# 28pins_Antariksh_unoR3_V1I1_Schematic.net
KiCad netlist of a schematic drawn in Altium Designer
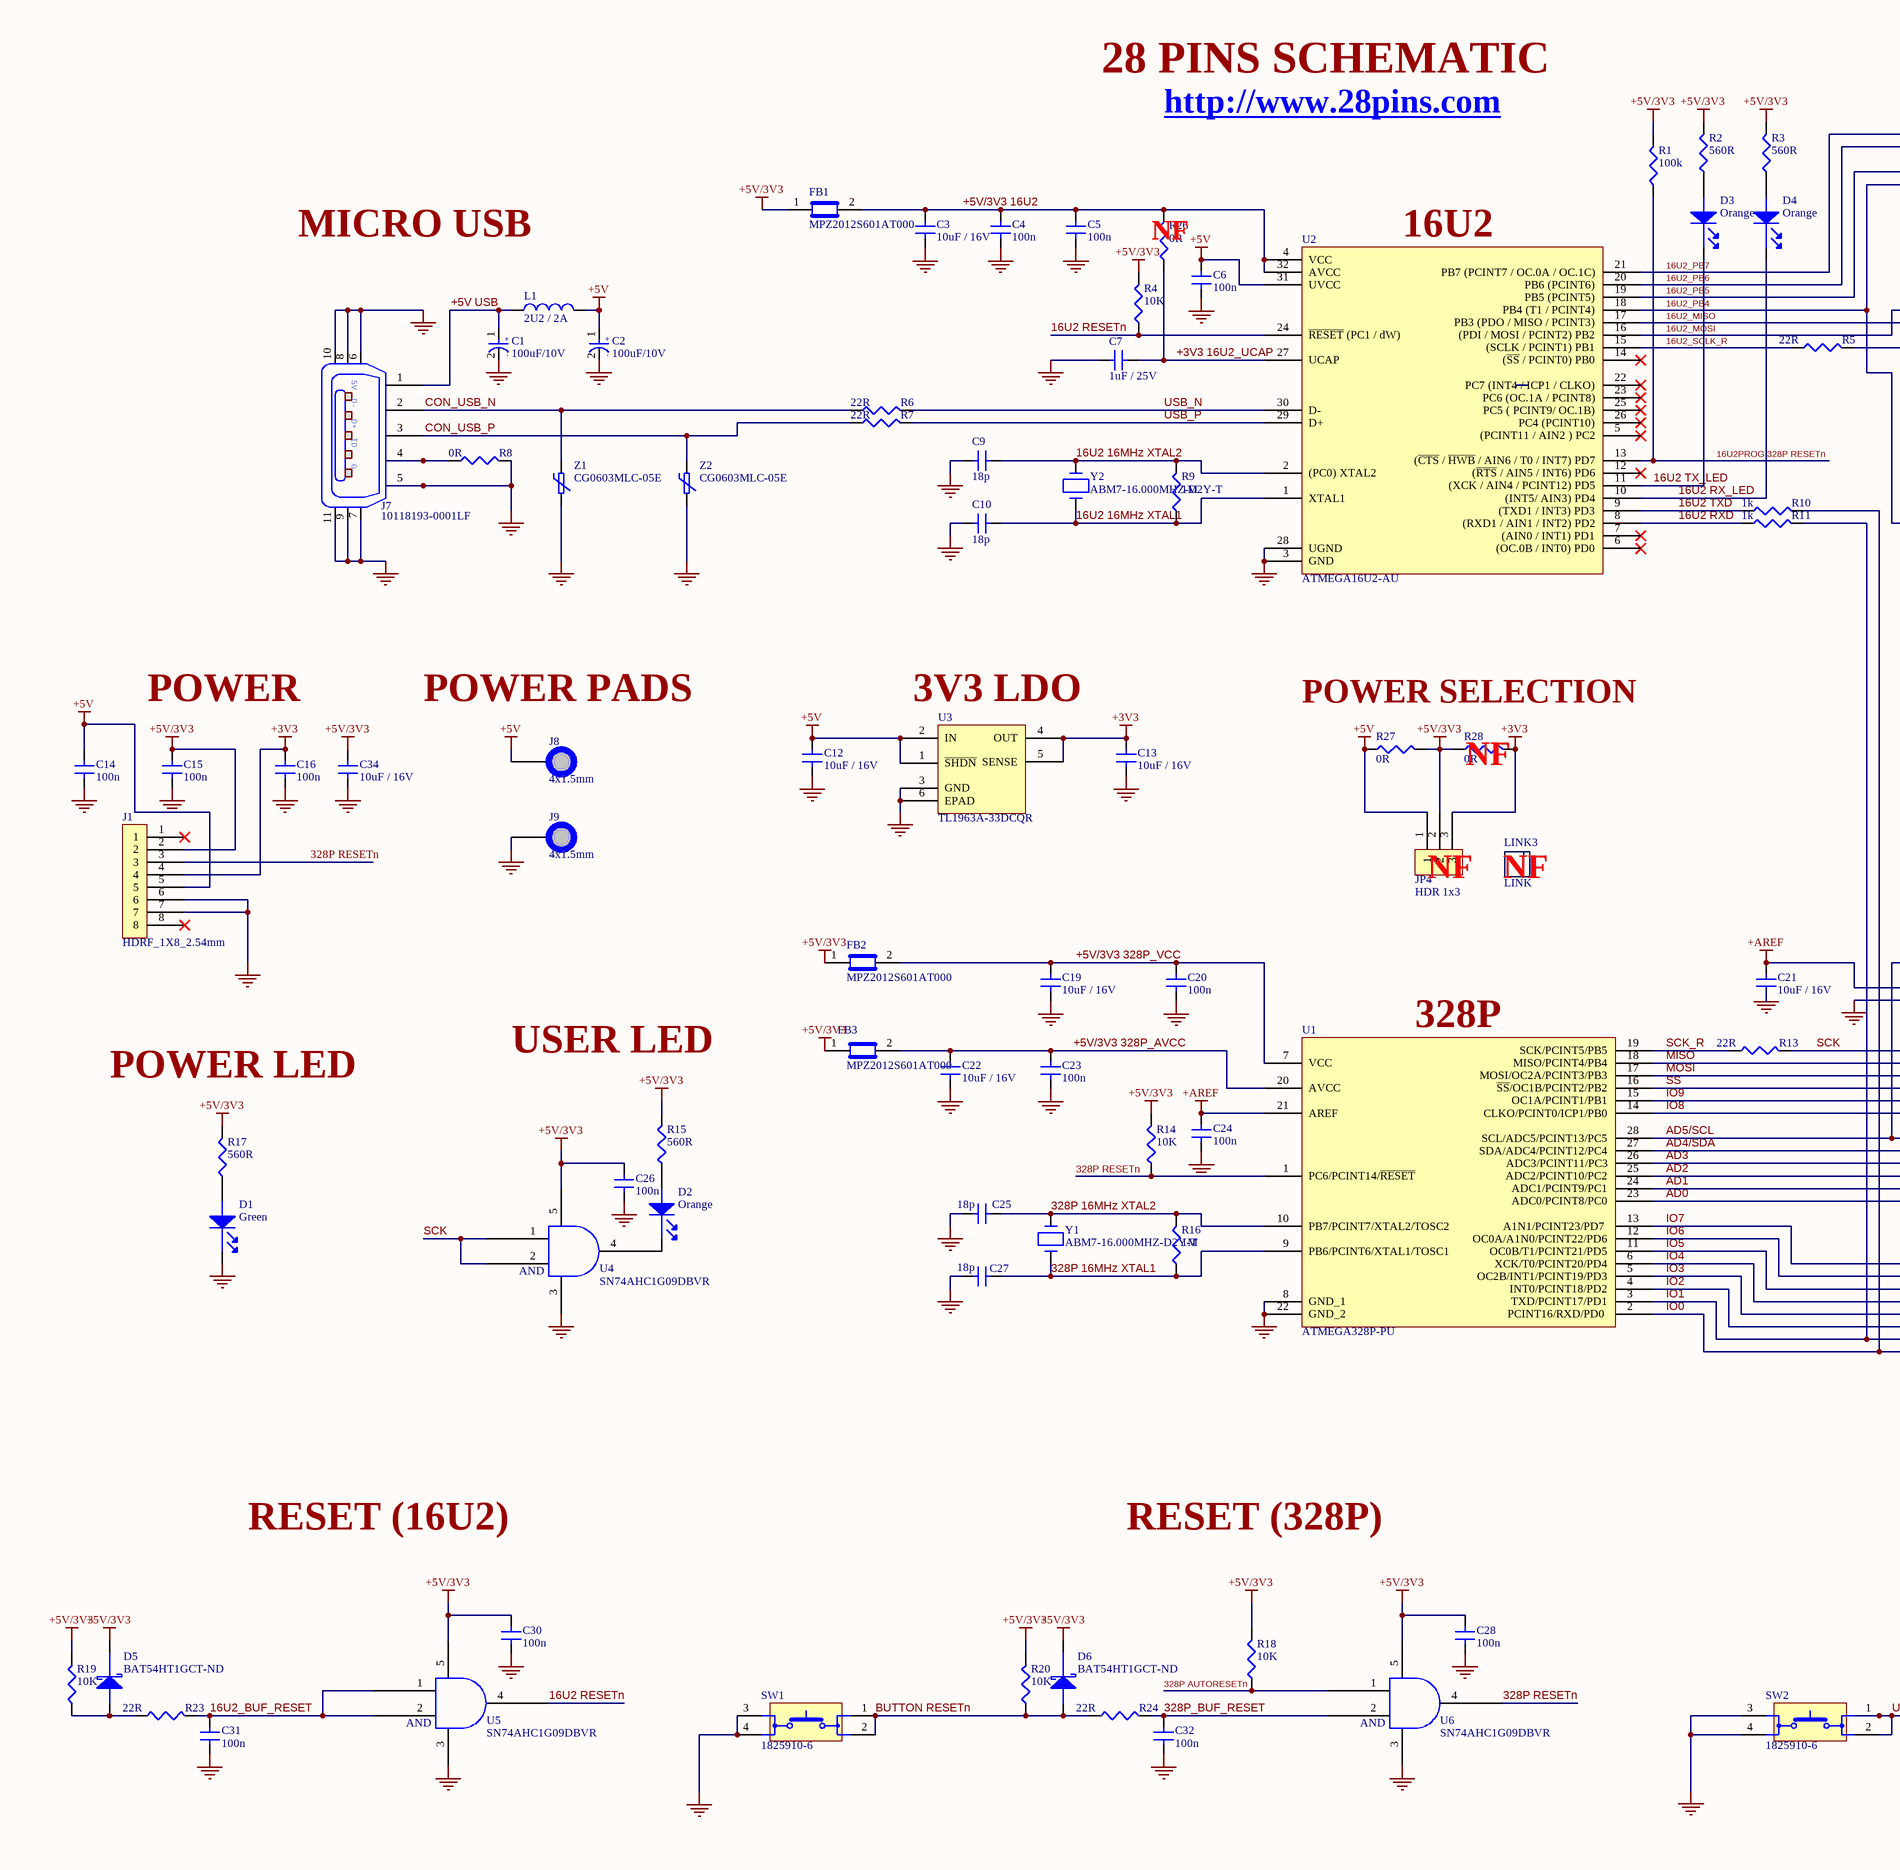
[diagram p0: 28pins_Antariksh_unoR3_V1I1_Schematic.SchDoc, left]
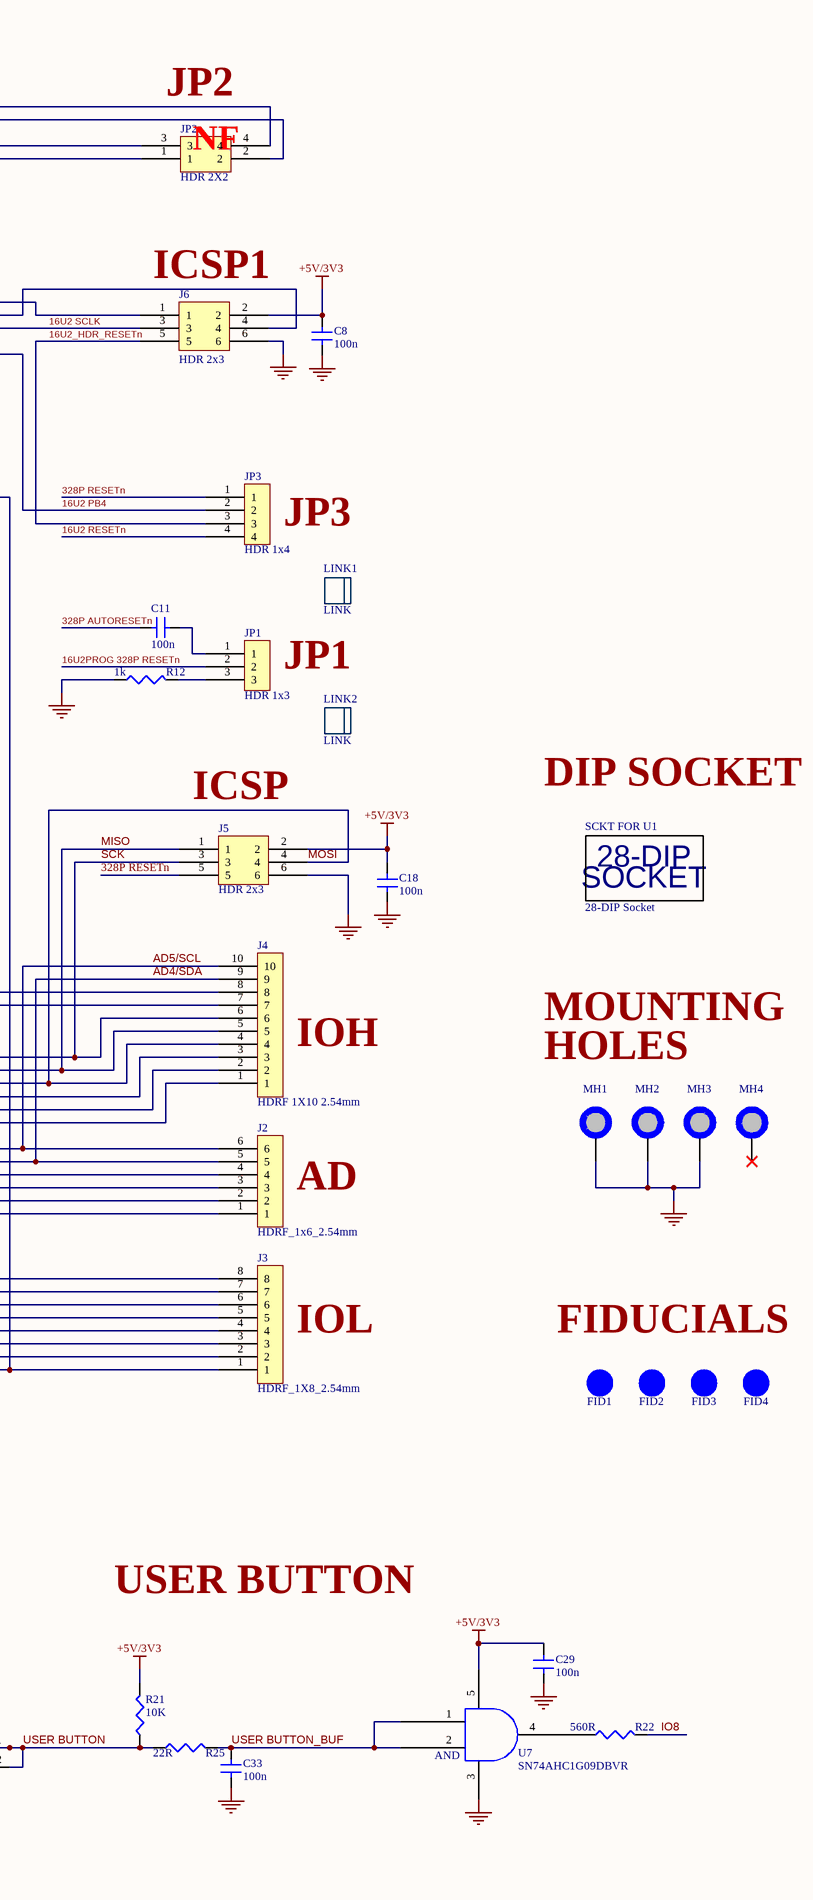
[diagram p1: 28pins_Antariksh_unoR3_V1I1_Schematic.SchDoc, right]

(export (version "E")
  (design (tool "Eeschema 10.0.6"))
  (components
    (comp (ref "C1")
      (value "100uF/10V")
      (footprint "C_ALU_C_SIZE")
      (description "Radial Can - SMD ALUMINUM ELECTROLYTIC CAPACITOR S 10V 100muF ±20% 0.197Dia 5.00mm")
      (fields
        (field (name "MANUFACTURER") "Panasonic")
        (field (name "MANUFACTURER PART NUMBER") "EEE-1AA101WR")
      )
      (libsource (lib "28pins_Antariksh_unoR3_V1I1_PCB") (part "EEE-1AA101WR"))
    )
    (comp (ref "C2")
      (value "100uF/10V")
      (footprint "C_ALU_C_SIZE")
      (description "Radial Can - SMD ALUMINUM ELECTROLYTIC CAPACITOR S 10V 100muF ±20% 0.197Dia 5.00mm")
      (fields
        (field (name "MANUFACTURER") "Panasonic")
        (field (name "MANUFACTURER PART NUMBER") "EEE-1AA101WR")
      )
      (libsource (lib "28pins_Antariksh_unoR3_V1I1_PCB") (part "EEE-1AA101WR"))
    )
    (comp (ref "C3")
      (value "10uF / 16V")
      (footprint "C0805")
      (fields
        (field (name "MANUFACTURER") "TDK")
        (field (name "MANUFACTURER PART NUMBER") "C2012X5R1C106M125AC")
        (field (name "TOLERANCE") "20%")
      )
      (libsource (lib "28pins_Antariksh_unoR3_V1I1_PCB") (part "C2012X5R1C106M125AC"))
    )
    (comp (ref "C4")
      (value "100n")
      (footprint "C0805")
      (description "C Series 0805 0.1 uF 50 V ±10 % Tolerance X7R SMT Multilayer Ceramic Capacitor")
      (fields
        (field (name "MANUFACTURER") "TDK")
        (field (name "MANUFACTURER PART NUMBER") "C2012X7R1H104K085AA")
      )
      (libsource (lib "28pins_Antariksh_unoR3_V1I1_PCB") (part "C2012X7R1H104K085AA"))
    )
    (comp (ref "C5")
      (value "100n")
      (footprint "C0805")
      (description "C Series 0805 0.1 uF 50 V ±10 % Tolerance X7R SMT Multilayer Ceramic Capacitor")
      (fields
        (field (name "MANUFACTURER") "TDK")
        (field (name "MANUFACTURER PART NUMBER") "C2012X7R1H104K085AA")
      )
      (libsource (lib "28pins_Antariksh_unoR3_V1I1_PCB") (part "C2012X7R1H104K085AA"))
    )
    (comp (ref "C6")
      (value "100n")
      (footprint "C0805")
      (description "C Series 0805 0.1 uF 50 V ±10 % Tolerance X7R SMT Multilayer Ceramic Capacitor")
      (fields
        (field (name "MANUFACTURER") "TDK")
        (field (name "MANUFACTURER PART NUMBER") "C2012X7R1H104K085AA")
      )
      (libsource (lib "28pins_Antariksh_unoR3_V1I1_PCB") (part "C2012X7R1H104K085AA"))
    )
    (comp (ref "C7")
      (value "1uF / 25V")
      (footprint "C0805")
      (description "C Series 0805 1 uF 25 V ±10% Tolerance X5R SMT Multilayer Ceramic Capacitor")
      (fields
        (field (name "MANUFACTURER") "TDK")
        (field (name "MANUFACTURER PART NUMBER") "C2012X5R1E105K125AA")
      )
      (libsource (lib "28pins_Antariksh_unoR3_V1I1_PCB") (part "C2012X5R1E105K125AA"))
    )
    (comp (ref "C8")
      (value "100n")
      (footprint "C0805")
      (description "C Series 0805 0.1 uF 50 V ±10 % Tolerance X7R SMT Multilayer Ceramic Capacitor")
      (fields
        (field (name "MANUFACTURER") "TDK")
        (field (name "MANUFACTURER PART NUMBER") "C2012X7R1H104K085AA")
      )
      (libsource (lib "28pins_Antariksh_unoR3_V1I1_PCB") (part "C2012X7R1H104K085AA"))
    )
    (comp (ref "C9")
      (value "18p")
      (footprint "C0805")
      (description "50V 120pF NP0 ±5% 0805 Multilayer Ceramic Capacitors MLCC - SMD/SMT ROHS")
      (fields
        (field (name "MANUFACTURER") "Yageo Group")
        (field (name "MANUFACTURER PART NUMBER") "CC0805JRNPO9BN121")
      )
      (libsource (lib "28pins_Antariksh_unoR3_V1I1_PCB") (part "CC0805JRNPO9BN121"))
    )
    (comp (ref "C10")
      (value "18p")
      (footprint "C0805")
      (description "50V 120pF NP0 ±5% 0805 Multilayer Ceramic Capacitors MLCC - SMD/SMT ROHS")
      (fields
        (field (name "MANUFACTURER") "Yageo Group")
        (field (name "MANUFACTURER PART NUMBER") "CC0805JRNPO9BN121")
      )
      (libsource (lib "28pins_Antariksh_unoR3_V1I1_PCB") (part "CC0805JRNPO9BN121"))
    )
    (comp (ref "C11")
      (value "100n")
      (footprint "C0805")
      (description "C Series 0805 0.1 uF 50 V ±10 % Tolerance X7R SMT Multilayer Ceramic Capacitor")
      (fields
        (field (name "MANUFACTURER") "TDK")
        (field (name "MANUFACTURER PART NUMBER") "C2012X7R1H104K085AA")
      )
      (libsource (lib "28pins_Antariksh_unoR3_V1I1_PCB") (part "C2012X7R1H104K085AA"))
    )
    (comp (ref "C12")
      (value "10uF / 16V")
      (footprint "C0805")
      (fields
        (field (name "MANUFACTURER") "TDK")
        (field (name "MANUFACTURER PART NUMBER") "C2012X5R1C106M125AC")
        (field (name "TOLERANCE") "20%")
      )
      (libsource (lib "28pins_Antariksh_unoR3_V1I1_PCB") (part "C2012X5R1C106M125AC"))
    )
    (comp (ref "C13")
      (value "10uF / 16V")
      (footprint "C0805")
      (fields
        (field (name "MANUFACTURER") "TDK")
        (field (name "MANUFACTURER PART NUMBER") "C2012X5R1C106M125AC")
        (field (name "TOLERANCE") "20%")
      )
      (libsource (lib "28pins_Antariksh_unoR3_V1I1_PCB") (part "C2012X5R1C106M125AC"))
    )
    (comp (ref "C14")
      (value "100n")
      (footprint "C0805")
      (description "C Series 0805 0.1 uF 50 V ±10 % Tolerance X7R SMT Multilayer Ceramic Capacitor")
      (fields
        (field (name "MANUFACTURER") "TDK")
        (field (name "MANUFACTURER PART NUMBER") "C2012X7R1H104K085AA")
      )
      (libsource (lib "28pins_Antariksh_unoR3_V1I1_PCB") (part "C2012X7R1H104K085AA"))
    )
    (comp (ref "C15")
      (value "100n")
      (footprint "C0805")
      (description "C Series 0805 0.1 uF 50 V ±10 % Tolerance X7R SMT Multilayer Ceramic Capacitor")
      (fields
        (field (name "MANUFACTURER") "TDK")
        (field (name "MANUFACTURER PART NUMBER") "C2012X7R1H104K085AA")
      )
      (libsource (lib "28pins_Antariksh_unoR3_V1I1_PCB") (part "C2012X7R1H104K085AA"))
    )
    (comp (ref "C16")
      (value "100n")
      (footprint "C0805")
      (description "C Series 0805 0.1 uF 50 V ±10 % Tolerance X7R SMT Multilayer Ceramic Capacitor")
      (fields
        (field (name "MANUFACTURER") "TDK")
        (field (name "MANUFACTURER PART NUMBER") "C2012X7R1H104K085AA")
      )
      (libsource (lib "28pins_Antariksh_unoR3_V1I1_PCB") (part "C2012X7R1H104K085AA"))
    )
    (comp (ref "C18")
      (value "100n")
      (footprint "C0805")
      (description "C Series 0805 0.1 uF 50 V ±10 % Tolerance X7R SMT Multilayer Ceramic Capacitor")
      (fields
        (field (name "MANUFACTURER") "TDK")
        (field (name "MANUFACTURER PART NUMBER") "C2012X7R1H104K085AA")
      )
      (libsource (lib "28pins_Antariksh_unoR3_V1I1_PCB") (part "C2012X7R1H104K085AA"))
    )
    (comp (ref "C19")
      (value "10uF / 16V")
      (footprint "C0805")
      (fields
        (field (name "MANUFACTURER") "TDK")
        (field (name "MANUFACTURER PART NUMBER") "C2012X5R1C106M125AC")
        (field (name "TOLERANCE") "20%")
      )
      (libsource (lib "28pins_Antariksh_unoR3_V1I1_PCB") (part "C2012X5R1C106M125AC"))
    )
    (comp (ref "C20")
      (value "100n")
      (footprint "C0805")
      (description "C Series 0805 0.1 uF 50 V ±10 % Tolerance X7R SMT Multilayer Ceramic Capacitor")
      (fields
        (field (name "MANUFACTURER") "TDK")
        (field (name "MANUFACTURER PART NUMBER") "C2012X7R1H104K085AA")
      )
      (libsource (lib "28pins_Antariksh_unoR3_V1I1_PCB") (part "C2012X7R1H104K085AA"))
    )
    (comp (ref "C21")
      (value "10uF / 16V")
      (footprint "C0805")
      (fields
        (field (name "MANUFACTURER") "TDK")
        (field (name "MANUFACTURER PART NUMBER") "C2012X5R1C106M125AC")
        (field (name "TOLERANCE") "20%")
      )
      (libsource (lib "28pins_Antariksh_unoR3_V1I1_PCB") (part "C2012X5R1C106M125AC"))
    )
    (comp (ref "C22")
      (value "10uF / 16V")
      (footprint "C0805")
      (fields
        (field (name "MANUFACTURER") "TDK")
        (field (name "MANUFACTURER PART NUMBER") "C2012X5R1C106M125AC")
        (field (name "TOLERANCE") "20%")
      )
      (libsource (lib "28pins_Antariksh_unoR3_V1I1_PCB") (part "C2012X5R1C106M125AC"))
    )
    (comp (ref "C23")
      (value "100n")
      (footprint "C0805")
      (description "C Series 0805 0.1 uF 50 V ±10 % Tolerance X7R SMT Multilayer Ceramic Capacitor")
      (fields
        (field (name "MANUFACTURER") "TDK")
        (field (name "MANUFACTURER PART NUMBER") "C2012X7R1H104K085AA")
      )
      (libsource (lib "28pins_Antariksh_unoR3_V1I1_PCB") (part "C2012X7R1H104K085AA"))
    )
    (comp (ref "C24")
      (value "100n")
      (footprint "C0805")
      (description "C Series 0805 0.1 uF 50 V ±10 % Tolerance X7R SMT Multilayer Ceramic Capacitor")
      (fields
        (field (name "MANUFACTURER") "TDK")
        (field (name "MANUFACTURER PART NUMBER") "C2012X7R1H104K085AA")
      )
      (libsource (lib "28pins_Antariksh_unoR3_V1I1_PCB") (part "C2012X7R1H104K085AA"))
    )
    (comp (ref "C25")
      (value "18p")
      (footprint "C0805")
      (description "50V 120pF NP0 ±5% 0805 Multilayer Ceramic Capacitors MLCC - SMD/SMT ROHS")
      (fields
        (field (name "MANUFACTURER") "Yageo Group")
        (field (name "MANUFACTURER PART NUMBER") "CC0805JRNPO9BN121")
      )
      (libsource (lib "28pins_Antariksh_unoR3_V1I1_PCB") (part "CC0805JRNPO9BN121"))
    )
    (comp (ref "C26")
      (value "100n")
      (footprint "C0805")
      (description "C Series 0805 0.1 uF 50 V ±10 % Tolerance X7R SMT Multilayer Ceramic Capacitor")
      (fields
        (field (name "MANUFACTURER") "TDK")
        (field (name "MANUFACTURER PART NUMBER") "C2012X7R1H104K085AA")
      )
      (libsource (lib "28pins_Antariksh_unoR3_V1I1_PCB") (part "C2012X7R1H104K085AA"))
    )
    (comp (ref "C27")
      (value "18p")
      (footprint "C0805")
      (description "50V 120pF NP0 ±5% 0805 Multilayer Ceramic Capacitors MLCC - SMD/SMT ROHS")
      (fields
        (field (name "MANUFACTURER") "Yageo Group")
        (field (name "MANUFACTURER PART NUMBER") "CC0805JRNPO9BN121")
      )
      (libsource (lib "28pins_Antariksh_unoR3_V1I1_PCB") (part "CC0805JRNPO9BN121"))
    )
    (comp (ref "C28")
      (value "100n")
      (footprint "C0805")
      (description "C Series 0805 0.1 uF 50 V ±10 % Tolerance X7R SMT Multilayer Ceramic Capacitor")
      (fields
        (field (name "MANUFACTURER") "TDK")
        (field (name "MANUFACTURER PART NUMBER") "C2012X7R1H104K085AA")
      )
      (libsource (lib "28pins_Antariksh_unoR3_V1I1_PCB") (part "C2012X7R1H104K085AA"))
    )
    (comp (ref "C29")
      (value "100n")
      (footprint "C0805")
      (description "C Series 0805 0.1 uF 50 V ±10 % Tolerance X7R SMT Multilayer Ceramic Capacitor")
      (fields
        (field (name "MANUFACTURER") "TDK")
        (field (name "MANUFACTURER PART NUMBER") "C2012X7R1H104K085AA")
      )
      (libsource (lib "28pins_Antariksh_unoR3_V1I1_PCB") (part "C2012X7R1H104K085AA"))
    )
    (comp (ref "C30")
      (value "100n")
      (footprint "C0805")
      (description "C Series 0805 0.1 uF 50 V ±10 % Tolerance X7R SMT Multilayer Ceramic Capacitor")
      (fields
        (field (name "MANUFACTURER") "TDK")
        (field (name "MANUFACTURER PART NUMBER") "C2012X7R1H104K085AA")
      )
      (libsource (lib "28pins_Antariksh_unoR3_V1I1_PCB") (part "C2012X7R1H104K085AA"))
    )
    (comp (ref "C31")
      (value "100n")
      (footprint "C0805")
      (description "C Series 0805 0.1 uF 50 V ±10 % Tolerance X7R SMT Multilayer Ceramic Capacitor")
      (fields
        (field (name "MANUFACTURER") "TDK")
        (field (name "MANUFACTURER PART NUMBER") "C2012X7R1H104K085AA")
      )
      (libsource (lib "28pins_Antariksh_unoR3_V1I1_PCB") (part "C2012X7R1H104K085AA"))
    )
    (comp (ref "C32")
      (value "100n")
      (footprint "C0805")
      (description "C Series 0805 0.1 uF 50 V ±10 % Tolerance X7R SMT Multilayer Ceramic Capacitor")
      (fields
        (field (name "MANUFACTURER") "TDK")
        (field (name "MANUFACTURER PART NUMBER") "C2012X7R1H104K085AA")
      )
      (libsource (lib "28pins_Antariksh_unoR3_V1I1_PCB") (part "C2012X7R1H104K085AA"))
    )
    (comp (ref "C33")
      (value "100n")
      (footprint "C0805")
      (description "C Series 0805 0.1 uF 50 V ±10 % Tolerance X7R SMT Multilayer Ceramic Capacitor")
      (fields
        (field (name "MANUFACTURER") "TDK")
        (field (name "MANUFACTURER PART NUMBER") "C2012X7R1H104K085AA")
      )
      (libsource (lib "28pins_Antariksh_unoR3_V1I1_PCB") (part "C2012X7R1H104K085AA"))
    )
    (comp (ref "C34")
      (value "10uF / 16V")
      (footprint "C0805")
      (fields
        (field (name "MANUFACTURER") "TDK")
        (field (name "MANUFACTURER PART NUMBER") "C2012X5R1C106M125AC")
        (field (name "TOLERANCE") "20%")
      )
      (libsource (lib "28pins_Antariksh_unoR3_V1I1_PCB") (part "C2012X5R1C106M125AC"))
    )
    (comp (ref "D1")
      (value "Green")
      (footprint "LED_0603")
      (description "LED Uni-Color Green 572nm 2-Pin Chip 0603(1608Metric) T/R")
      (fields
        (field (name "MANUFACTURER") "Osram")
        (field (name "MANUFACTURER PART NUMBER") "LG L29K-G2J1-24-0-2-R18-Z")
      )
      (libsource (lib "28pins_Antariksh_unoR3_V1I1_PCB") (part "LG L29K-G2J1-24-0-2-R18-Z"))
    )
    (comp (ref "D2")
      (value "Orange")
      (footprint "LED_0603")
      (description "LED Uni-Color Orange 610nm Automotive 2-Pin Chip 0603(1608Metric) T/R")
      (fields
        (field (name "MANUFACTURER") "Osram")
        (field (name "MANUFACTURER PART NUMBER") "LO L29K-H2K1-24-0-2-R18-Z")
      )
      (libsource (lib "28pins_Antariksh_unoR3_V1I1_PCB") (part "LO L29K-H2K1-24-0-2-R18-Z"))
    )
    (comp (ref "D3")
      (value "Orange")
      (footprint "LED_0603")
      (description "LED Uni-Color Orange 610nm Automotive 2-Pin Chip 0603(1608Metric) T/R")
      (fields
        (field (name "MANUFACTURER") "Osram")
        (field (name "MANUFACTURER PART NUMBER") "LO L29K-H2K1-24-0-2-R18-Z")
      )
      (libsource (lib "28pins_Antariksh_unoR3_V1I1_PCB") (part "LO L29K-H2K1-24-0-2-R18-Z"))
    )
    (comp (ref "D4")
      (value "Orange")
      (footprint "LED_0603")
      (description "LED Uni-Color Orange 610nm Automotive 2-Pin Chip 0603(1608Metric) T/R")
      (fields
        (field (name "MANUFACTURER") "Osram")
        (field (name "MANUFACTURER PART NUMBER") "LO L29K-H2K1-24-0-2-R18-Z")
      )
      (libsource (lib "28pins_Antariksh_unoR3_V1I1_PCB") (part "LO L29K-H2K1-24-0-2-R18-Z"))
    )
    (comp (ref "D5")
      (value "BAT54HT1GCT-ND")
      (footprint "SOD323")
      (description "Small Signal Schottky Diode, Single, 30 V, 200 Ma, 800 Mv, 600 Ma, 150 C")
      (fields (field (name "MANUFACTURER") "onsemi") (field (name "MANUFACTURER PART NUMBER") "BAT54HT1G"))
      (libsource (lib "28pins_Antariksh_unoR3_V1I1_PCB") (part "BAT54HT1G"))
    )
    (comp (ref "D6")
      (value "BAT54HT1GCT-ND")
      (footprint "SOD323")
      (description "Small Signal Schottky Diode, Single, 30 V, 200 Ma, 800 Mv, 600 Ma, 150 C")
      (fields (field (name "MANUFACTURER") "onsemi") (field (name "MANUFACTURER PART NUMBER") "BAT54HT1G"))
      (libsource (lib "28pins_Antariksh_unoR3_V1I1_PCB") (part "BAT54HT1G"))
    )
    (comp (ref "FB1")
      (value "MPZ2012S601AT000")
      (footprint "C0805")
      (description "Ferrite Beads Multi-Layer Power 600Ohm 25% 100MHz 2A 100mOhm DCR 0805 T/R")
      (fields (field (name "MANUFACTURER") "TDK") (field (name "TOLERANCE") "25%"))
      (libsource (lib "28pins_Antariksh_unoR3_V1I1_PCB") (part "MPZ2012S601AT000"))
    )
    (comp (ref "FB2")
      (value "MPZ2012S601AT000")
      (footprint "C0805")
      (description "Ferrite Beads Multi-Layer Power 600Ohm 25% 100MHz 2A 100mOhm DCR 0805 T/R")
      (fields (field (name "MANUFACTURER") "TDK") (field (name "TOLERANCE") "25%"))
      (libsource (lib "28pins_Antariksh_unoR3_V1I1_PCB") (part "MPZ2012S601AT000"))
    )
    (comp (ref "FB3")
      (value "MPZ2012S601AT000")
      (footprint "C0805")
      (description "Ferrite Beads Multi-Layer Power 600Ohm 25% 100MHz 2A 100mOhm DCR 0805 T/R")
      (fields (field (name "MANUFACTURER") "TDK") (field (name "TOLERANCE") "25%"))
      (libsource (lib "28pins_Antariksh_unoR3_V1I1_PCB") (part "MPZ2012S601AT000"))
    )
    (comp (ref "FID1")
      (value "FID_1mm")
      (footprint "FID_40x120")
      (description "Fiducial 40mil Diameter, 120mil Mask")
      (libsource (lib "28pins_Antariksh_unoR3_V1I1_PCB") (part "FID_1mm"))
    )
    (comp (ref "FID2")
      (value "FID_1mm")
      (footprint "FID_40x120")
      (description "Fiducial 40mil Diameter, 120mil Mask")
      (libsource (lib "28pins_Antariksh_unoR3_V1I1_PCB") (part "FID_1mm"))
    )
    (comp (ref "FID3")
      (value "FID_1mm")
      (footprint "FID_40x120")
      (description "Fiducial 40mil Diameter, 120mil Mask")
      (libsource (lib "28pins_Antariksh_unoR3_V1I1_PCB") (part "FID_1mm"))
    )
    (comp (ref "FID4")
      (value "FID_1mm")
      (footprint "FID_40x120")
      (description "Fiducial 40mil Diameter, 120mil Mask")
      (libsource (lib "28pins_Antariksh_unoR3_V1I1_PCB") (part "FID_1mm"))
    )
    (comp (ref "J1")
      (value "HDRF_1X8_2.54mm")
      (footprint "HDR_F_1X8_2.54mm")
      (description "2.54mm (0.1) Pitch SIL Vertical PC Tail Socket Assembly, selective gold + tin, 8 contacts\"")
      (fields (field (name "MANUFACTURER") "Harwin") (field (name "MANUFACTURER PART NUMBER") "M20-7820842"))
      (libsource (lib "28pins_Antariksh_unoR3_V1I1_PCB") (part "M20-7820842"))
    )
    (comp (ref "J2")
      (value "HDRF_1x6_2.54mm")
      (footprint "HDR_F_1X6_2.54mm")
      (description "Conn Socket Strip Receptacle 6 Position 2.54mm Solder Straight Through Hole Tube")
      (fields (field (name "MANUFACTURER") "Harwin") (field (name "MANUFACTURER PART NUMBER") "M20-7820646"))
      (libsource (lib "28pins_Antariksh_unoR3_V1I1_PCB") (part "M20-7820646"))
    )
    (comp (ref "J3")
      (value "HDRF_1X8_2.54mm")
      (footprint "HDR_F_1X8_2.54mm")
      (description "2.54mm (0.1) Pitch SIL Vertical PC Tail Socket Assembly, selective gold + tin, 8 contacts\"")
      (fields (field (name "MANUFACTURER") "Harwin") (field (name "MANUFACTURER PART NUMBER") "M20-7820842"))
      (libsource (lib "") (part "M20-7820842_1"))
    )
    (comp (ref "J4")
      (value "HDRF 1X10 2.54mm")
      (footprint "HDR_F_1X10_2.54mm")
      (description "Conn Socket Strip Receptacle 10 Position 2.54mm Solder Straight Through Hole Tube")
      (fields (field (name "MANUFACTURER") "Harwin") (field (name "MANUFACTURER PART NUMBER") "M20-7821046"))
      (libsource (lib "28pins_Antariksh_unoR3_V1I1_PCB") (part "M20-7821046"))
    )
    (comp (ref "J5")
      (value "HDR 2x3")
      (footprint "HDR_2x3_2.54mm")
      (description "Conn; Rect; Header; Unshrouded; 6 Pos; 2.54mm Pitch; 2-Row; Thru-Hole; BergStik")
      (fields
        (field (name "MANUFACTURER") "Amphenol Communications Solutions")
        (field (name "MANUFACTURER PART NUMBER") "67997-106HLF")
      )
      (libsource (lib "28pins_Antariksh_unoR3_V1I1_PCB") (part "67997-106HLF"))
    )
    (comp (ref "J6")
      (value "HDR 2x3")
      (footprint "HDR_2x3_2.54mm")
      (description "Conn; Rect; Header; Unshrouded; 6 Pos; 2.54mm Pitch; 2-Row; Thru-Hole; BergStik")
      (fields
        (field (name "MANUFACTURER") "Amphenol Communications Solutions")
        (field (name "MANUFACTURER PART NUMBER") "67997-106HLF")
      )
      (libsource (lib "28pins_Antariksh_unoR3_V1I1_PCB") (part "67997-106HLF"))
    )
    (comp (ref "J7")
      (value "10118193-0001LF")
      (footprint "10118193")
      (description "USB - micro B USB 2.0 Receptacle Connector 5 Position Surface Mount, Right Angle, Horizontal")
      (fields (field (name "MANUFACTURER") "Amphenol Communications Solutions"))
      (libsource (lib "28pins_Antariksh_unoR3_V1I1_PCB") (part "10118193-0001LF"))
    )
    (comp (ref "J8")
      (value "4x1.5mm")
      (footprint "PAD_WITH_HOLE_4x1.5mm")
      (description "PAD WITH A HOLE 4x1.5mm")
      (libsource (lib "28pins_Antariksh_unoR3_V1I1_PCB") (part "PAD_WITH_HOLE_4x1.5mm"))
    )
    (comp (ref "J9")
      (value "4x1.5mm")
      (footprint "PAD_WITH_HOLE_4x1.5mm")
      (description "PAD WITH A HOLE 4x1.5mm")
      (libsource (lib "28pins_Antariksh_unoR3_V1I1_PCB") (part "PAD_WITH_HOLE_4x1.5mm"))
    )
    (comp (ref "JP1")
      (value "HDR 1x3")
      (footprint "HDR_1X3_2.54mm")
      (description "Conn Unshrouded Header HDR 3 POS 2.54mm Solder ST Top Entry Thru-Hole BergStik® Bulk")
      (fields
        (field (name "MANUFACTURER") "Amphenol Communications Solutions")
        (field (name "MANUFACTURER PART NUMBER") "68000-103HLF")
      )
      (libsource (lib "") (part "68000-103HLF_1"))
    )
    (comp (ref "JP2")
      (value "HDR 2X2")
      (footprint "HDR_2x2_2.54mm")
      (description "Conn Unshrouded Header HDR 4 POS 2.54mm Solder ST Top Entry Thru-Hole BergStik® Bulk")
      (fields
        (field (name "MANUFACTURER") "Amphenol Communications Solutions")
        (field (name "MANUFACTURER PART NUMBER") "67996-104HLF")
      )
      (libsource (lib "28pins_Antariksh_unoR3_V1I1_PCB") (part "67996-104HLF"))
    )
    (comp (ref "JP3")
      (value "HDR 1x4")
      (footprint "HDR_1X4_2.54mm")
      (description "Conn Unshrouded Header HDR 4 POS 2.54mm Solder ST Top Entry Thru-Hole BergStik® Bulk")
      (fields
        (field (name "MANUFACTURER") "Amphenol Communications Solutions")
        (field (name "MANUFACTURER PART NUMBER") "68001-204HLF")
      )
      (libsource (lib "28pins_Antariksh_unoR3_V1I1_PCB") (part "68001-204HLF"))
    )
    (comp (ref "JP4")
      (value "HDR 1x3")
      (footprint "HDR_1X3_2.54mm")
      (description "Conn Unshrouded Header HDR 3 POS 2.54mm Solder ST Top Entry Thru-Hole BergStik® Bulk")
      (fields
        (field (name "MANUFACTURER") "Amphenol Communications Solutions")
        (field (name "MANUFACTURER PART NUMBER") "68000-103HLF")
      )
      (libsource (lib "28pins_Antariksh_unoR3_V1I1_PCB") (part "68000-103HLF"))
    )
    (comp (ref "L1")
      (value "2U2 / 2A")
      (footprint "CL210_IND")
      (description "General Purpose Inductor, 2.2uH, 20%, 1 Element, Ferrite-Core, SMD, 1210")
      (fields
        (field (name "MANUFACTURER") "KEMET")
        (field (name "MANUFACTURER PART NUMBER") "L1210R2R2MDWIT")
      )
      (libsource (lib "28pins_Antariksh_unoR3_V1I1_PCB") (part "L1210R2R2MDWIT"))
    )
    (comp (ref "LINK1")
      (value "LINK")
      (description "2 Position 2.54 mm Centerline Single Circuit Open Top Jumper")
      (fields
        (field (name "MANUFACTURER") "Sullins")
        (field (name "MANUFACTURER PART NUMBER") "QPC02SXGN-RC")
      )
      (libsource (lib "28pins_Antariksh_unoR3_V1I1_PCB") (part "QPC02SXGN-RC"))
    )
    (comp (ref "LINK2")
      (value "LINK")
      (description "2 Position 2.54 mm Centerline Single Circuit Open Top Jumper")
      (fields
        (field (name "MANUFACTURER") "Sullins")
        (field (name "MANUFACTURER PART NUMBER") "QPC02SXGN-RC")
      )
      (libsource (lib "28pins_Antariksh_unoR3_V1I1_PCB") (part "QPC02SXGN-RC"))
    )
    (comp (ref "LINK3")
      (value "LINK")
      (description "2 Position 2.54 mm Centerline Single Circuit Open Top Jumper")
      (fields
        (field (name "MANUFACTURER") "Sullins")
        (field (name "MANUFACTURER PART NUMBER") "QPC02SXGN-RC")
      )
      (libsource (lib "28pins_Antariksh_unoR3_V1I1_PCB") (part "QPC02SXGN-RC"))
    )
    (comp (ref "MH1")
      (value "MH_7.4mmCX3.2mmD")
      (footprint "MH_7.4mmCx3.2mmD")
      (description "Mounting Hole 7.4mm Diameter, 3.2mm Drill")
      (libsource (lib "28pins_Antariksh_unoR3_V1I1_PCB") (part "MH_7.4mmCx2.3mmD"))
    )
    (comp (ref "MH2")
      (value "MH_7.4mmCX3.2mmD")
      (footprint "MH_7.4mmCx3.2mmD")
      (description "Mounting Hole 7.4mm Diameter, 3.2mm Drill")
      (libsource (lib "28pins_Antariksh_unoR3_V1I1_PCB") (part "MH_7.4mmCx2.3mmD"))
    )
    (comp (ref "MH3")
      (value "MH_7.4mmCX3.2mmD")
      (footprint "MH_7.4mmCx3.2mmD")
      (description "Mounting Hole 7.4mm Diameter, 3.2mm Drill")
      (libsource (lib "28pins_Antariksh_unoR3_V1I1_PCB") (part "MH_7.4mmCx2.3mmD"))
    )
    (comp (ref "MH4")
      (value "MH_7.4mmNCx2.3mmD")
      (footprint "MH_7.4mmNCx3.2mmD")
      (description "Mounting Hole 7.4mm Diameter (Non-Copper), 3.2mm Drill (Non-Plated)")
      (libsource (lib "28pins_Antariksh_unoR3_V1I1_PCB") (part "MH_7.4mmNCx2.3mmD"))
    )
    (comp (ref "R1")
      (value "100k")
      (footprint "R0805")
      (description "125mW Thick Film Resistors 150V ±100ppm/℃ ±1% 100kΩ 0805 Chip Resistor - Surface Mount ROHS")
      (fields
        (field (name "MANUFACTURER") "Yageo Group")
        (field (name "MANUFACTURER PART NUMBER") "RC0805FR-07100KL")
      )
      (libsource (lib "28pins_Antariksh_unoR3_V1I1_PCB") (part "RC0805FR-07100KL"))
    )
    (comp (ref "R2")
      (value "560R")
      (footprint "R0805")
      (description "Res Thick Film 0805 560 Ohm 1% 0.125W(1/8W) ±100ppm/C Pad SMD T/R")
      (fields
        (field (name "MANUFACTURER") "Yageo Group")
        (field (name "MANUFACTURER PART NUMBER") "RC0805FR-07560RL")
      )
      (libsource (lib "28pins_Antariksh_unoR3_V1I1_PCB") (part "RC0805FR-07560RL"))
    )
    (comp (ref "R3")
      (value "560R")
      (footprint "R0805")
      (description "Res Thick Film 0805 560 Ohm 1% 0.125W(1/8W) ±100ppm/C Pad SMD T/R")
      (fields
        (field (name "MANUFACTURER") "Yageo Group")
        (field (name "MANUFACTURER PART NUMBER") "RC0805FR-07560RL")
      )
      (libsource (lib "28pins_Antariksh_unoR3_V1I1_PCB") (part "RC0805FR-07560RL"))
    )
    (comp (ref "R4")
      (value "10K")
      (footprint "R0805")
      (description "Res Thick Film 0805 10K Ohm 1% 0.125W(1/8W) +/-100ppm/C Epoxy Pad SMD T/R")
      (fields
        (field (name "MANUFACTURER") "Yageo Group")
        (field (name "MANUFACTURER PART NUMBER") "RC0805FR-0710KL")
      )
      (libsource (lib "28pins_Antariksh_unoR3_V1I1_PCB") (part "RC0805FR-0710KL"))
    )
    (comp (ref "R5")
      (value "22R")
      (footprint "R0805")
      (description "125mW Thick Film Resistors 150V ±100ppm/℃ ±1% 22Ω 0805 Chip Resistor - Surface Mount ROHS")
      (fields
        (field (name "MANUFACTURER") "Yageo Group")
        (field (name "MANUFACTURER PART NUMBER") "RC0805FR-0722RL")
      )
      (libsource (lib "28pins_Antariksh_unoR3_V1I1_PCB") (part "RC0805FR-0722RL"))
    )
    (comp (ref "R6")
      (value "22R")
      (footprint "R0805")
      (description "125mW Thick Film Resistors 150V ±100ppm/℃ ±1% 22Ω 0805 Chip Resistor - Surface Mount ROHS")
      (fields
        (field (name "MANUFACTURER") "Yageo Group")
        (field (name "MANUFACTURER PART NUMBER") "RC0805FR-0722RL")
      )
      (libsource (lib "28pins_Antariksh_unoR3_V1I1_PCB") (part "RC0805FR-0722RL"))
    )
    (comp (ref "R7")
      (value "22R")
      (footprint "R0805")
      (description "125mW Thick Film Resistors 150V ±100ppm/℃ ±1% 22Ω 0805 Chip Resistor - Surface Mount ROHS")
      (fields
        (field (name "MANUFACTURER") "Yageo Group")
        (field (name "MANUFACTURER PART NUMBER") "RC0805FR-0722RL")
      )
      (libsource (lib "28pins_Antariksh_unoR3_V1I1_PCB") (part "RC0805FR-0722RL"))
    )
    (comp (ref "R8")
      (value "0R")
      (footprint "R0805")
      (description "GENERAL PURPOSE CHIP RESISTOR Metal Glaze/thick Film, 0.125W, 0ohm, Surface Mount, 0805")
      (fields
        (field (name "MANUFACTURER") "Yageo Group")
        (field (name "MANUFACTURER PART NUMBER") "RC0805JR-070RL")
      )
      (libsource (lib "28pins_Antariksh_unoR3_V1I1_PCB") (part "RC0805JR-070RL"))
    )
    (comp (ref "R9")
      (value "1M")
      (footprint "R0805")
      (description "125Mw Thick Film Resistors 100Ppm/ 1% 1M 0805 Chip Resistor Surface Mount Rohs")
      (fields
        (field (name "MANUFACTURER") "Yageo Group")
        (field (name "MANUFACTURER PART NUMBER") "RC0805FR-071ML")
      )
      (libsource (lib "28pins_Antariksh_unoR3_V1I1_PCB") (part "RC0805FR-071ML"))
    )
    (comp (ref "R10")
      (value "1k")
      (footprint "R0805")
      (description "125Mw Thick Film Resistors 100Ppm/ 1% 1K 0805 Chip Resistor Surface Mount Rohs")
      (fields
        (field (name "MANUFACTURER") "Yageo Group")
        (field (name "MANUFACTURER PART NUMBER") "RC0805FR-071KL")
      )
      (libsource (lib "28pins_Antariksh_unoR3_V1I1_PCB") (part "RC0805FR-071KL"))
    )
    (comp (ref "R11")
      (value "1k")
      (footprint "R0805")
      (description "125Mw Thick Film Resistors 100Ppm/ 1% 1K 0805 Chip Resistor Surface Mount Rohs")
      (fields
        (field (name "MANUFACTURER") "Yageo Group")
        (field (name "MANUFACTURER PART NUMBER") "RC0805FR-071KL")
      )
      (libsource (lib "28pins_Antariksh_unoR3_V1I1_PCB") (part "RC0805FR-071KL"))
    )
    (comp (ref "R12")
      (value "1k")
      (footprint "R0805")
      (description "125Mw Thick Film Resistors 100Ppm/ 1% 1K 0805 Chip Resistor Surface Mount Rohs")
      (fields
        (field (name "MANUFACTURER") "Yageo Group")
        (field (name "MANUFACTURER PART NUMBER") "RC0805FR-071KL")
      )
      (libsource (lib "28pins_Antariksh_unoR3_V1I1_PCB") (part "RC0805FR-071KL"))
    )
    (comp (ref "R13")
      (value "22R")
      (footprint "R0805")
      (description "125mW Thick Film Resistors 150V ±100ppm/℃ ±1% 22Ω 0805 Chip Resistor - Surface Mount ROHS")
      (fields
        (field (name "MANUFACTURER") "Yageo Group")
        (field (name "MANUFACTURER PART NUMBER") "RC0805FR-0722RL")
      )
      (libsource (lib "28pins_Antariksh_unoR3_V1I1_PCB") (part "RC0805FR-0722RL"))
    )
    (comp (ref "R14")
      (value "10K")
      (footprint "R0805")
      (description "Res Thick Film 0805 10K Ohm 1% 0.125W(1/8W) +/-100ppm/C Epoxy Pad SMD T/R")
      (fields
        (field (name "MANUFACTURER") "Yageo Group")
        (field (name "MANUFACTURER PART NUMBER") "RC0805FR-0710KL")
      )
      (libsource (lib "28pins_Antariksh_unoR3_V1I1_PCB") (part "RC0805FR-0710KL"))
    )
    (comp (ref "R15")
      (value "560R")
      (footprint "R0805")
      (description "Res Thick Film 0805 560 Ohm 1% 0.125W(1/8W) ±100ppm/C Pad SMD T/R")
      (fields
        (field (name "MANUFACTURER") "Yageo Group")
        (field (name "MANUFACTURER PART NUMBER") "RC0805FR-07560RL")
      )
      (libsource (lib "28pins_Antariksh_unoR3_V1I1_PCB") (part "RC0805FR-07560RL"))
    )
    (comp (ref "R16")
      (value "1M")
      (footprint "R0805")
      (description "125Mw Thick Film Resistors 100Ppm/ 1% 1M 0805 Chip Resistor Surface Mount Rohs")
      (fields
        (field (name "MANUFACTURER") "Yageo Group")
        (field (name "MANUFACTURER PART NUMBER") "RC0805FR-071ML")
      )
      (libsource (lib "28pins_Antariksh_unoR3_V1I1_PCB") (part "RC0805FR-071ML"))
    )
    (comp (ref "R17")
      (value "560R")
      (footprint "R0805")
      (description "Res Thick Film 0805 560 Ohm 1% 0.125W(1/8W) ±100ppm/C Pad SMD T/R")
      (fields
        (field (name "MANUFACTURER") "Yageo Group")
        (field (name "MANUFACTURER PART NUMBER") "RC0805FR-07560RL")
      )
      (libsource (lib "28pins_Antariksh_unoR3_V1I1_PCB") (part "RC0805FR-07560RL"))
    )
    (comp (ref "R18")
      (value "10K")
      (footprint "R0805")
      (description "Res Thick Film 0805 10K Ohm 1% 0.125W(1/8W) +/-100ppm/C Epoxy Pad SMD T/R")
      (fields
        (field (name "MANUFACTURER") "Yageo Group")
        (field (name "MANUFACTURER PART NUMBER") "RC0805FR-0710KL")
      )
      (libsource (lib "28pins_Antariksh_unoR3_V1I1_PCB") (part "RC0805FR-0710KL"))
    )
    (comp (ref "R19")
      (value "10K")
      (footprint "R0805")
      (description "Res Thick Film 0805 10K Ohm 1% 0.125W(1/8W) +/-100ppm/C Epoxy Pad SMD T/R")
      (fields
        (field (name "MANUFACTURER") "Yageo Group")
        (field (name "MANUFACTURER PART NUMBER") "RC0805FR-0710KL")
      )
      (libsource (lib "28pins_Antariksh_unoR3_V1I1_PCB") (part "RC0805FR-0710KL"))
    )
    (comp (ref "R20")
      (value "10K")
      (footprint "R0805")
      (description "Res Thick Film 0805 10K Ohm 1% 0.125W(1/8W) +/-100ppm/C Epoxy Pad SMD T/R")
      (fields
        (field (name "MANUFACTURER") "Yageo Group")
        (field (name "MANUFACTURER PART NUMBER") "RC0805FR-0710KL")
      )
      (libsource (lib "28pins_Antariksh_unoR3_V1I1_PCB") (part "RC0805FR-0710KL"))
    )
    (comp (ref "R21")
      (value "10K")
      (footprint "R0805")
      (description "Res Thick Film 0805 10K Ohm 1% 0.125W(1/8W) +/-100ppm/C Epoxy Pad SMD T/R")
      (fields
        (field (name "MANUFACTURER") "Yageo Group")
        (field (name "MANUFACTURER PART NUMBER") "RC0805FR-0710KL")
      )
      (libsource (lib "28pins_Antariksh_unoR3_V1I1_PCB") (part "RC0805FR-0710KL"))
    )
    (comp (ref "R22")
      (value "560R")
      (footprint "R0805")
      (description "Res Thick Film 0805 560 Ohm 1% 0.125W(1/8W) ±100ppm/C Pad SMD T/R")
      (fields
        (field (name "MANUFACTURER") "Yageo Group")
        (field (name "MANUFACTURER PART NUMBER") "RC0805FR-07560RL")
      )
      (libsource (lib "28pins_Antariksh_unoR3_V1I1_PCB") (part "RC0805FR-07560RL"))
    )
    (comp (ref "R23")
      (value "22R")
      (footprint "R0805")
      (description "125mW Thick Film Resistors 150V ±100ppm/℃ ±1% 22Ω 0805 Chip Resistor - Surface Mount ROHS")
      (fields
        (field (name "MANUFACTURER") "Yageo Group")
        (field (name "MANUFACTURER PART NUMBER") "RC0805FR-0722RL")
      )
      (libsource (lib "28pins_Antariksh_unoR3_V1I1_PCB") (part "RC0805FR-0722RL"))
    )
    (comp (ref "R24")
      (value "22R")
      (footprint "R0805")
      (description "125mW Thick Film Resistors 150V ±100ppm/℃ ±1% 22Ω 0805 Chip Resistor - Surface Mount ROHS")
      (fields
        (field (name "MANUFACTURER") "Yageo Group")
        (field (name "MANUFACTURER PART NUMBER") "RC0805FR-0722RL")
      )
      (libsource (lib "28pins_Antariksh_unoR3_V1I1_PCB") (part "RC0805FR-0722RL"))
    )
    (comp (ref "R25")
      (value "22R")
      (footprint "R0805")
      (description "125mW Thick Film Resistors 150V ±100ppm/℃ ±1% 22Ω 0805 Chip Resistor - Surface Mount ROHS")
      (fields
        (field (name "MANUFACTURER") "Yageo Group")
        (field (name "MANUFACTURER PART NUMBER") "RC0805FR-0722RL")
      )
      (libsource (lib "28pins_Antariksh_unoR3_V1I1_PCB") (part "RC0805FR-0722RL"))
    )
    (comp (ref "R26")
      (value "0R")
      (footprint "R0805")
      (description "GENERAL PURPOSE CHIP RESISTOR Metal Glaze/thick Film, 0.125W, 0ohm, Surface Mount, 0805")
      (fields
        (field (name "MANUFACTURER") "Yageo Group")
        (field (name "MANUFACTURER PART NUMBER") "RC0805JR-070RL")
      )
      (libsource (lib "28pins_Antariksh_unoR3_V1I1_PCB") (part "RC0805JR-070RL"))
    )
    (comp (ref "R27")
      (value "0R")
      (footprint "R0805")
      (description "GENERAL PURPOSE CHIP RESISTOR Metal Glaze/thick Film, 0.125W, 0ohm, Surface Mount, 0805")
      (fields
        (field (name "MANUFACTURER") "Yageo Group")
        (field (name "MANUFACTURER PART NUMBER") "RC0805JR-070RL")
      )
      (libsource (lib "28pins_Antariksh_unoR3_V1I1_PCB") (part "RC0805JR-070RL"))
    )
    (comp (ref "R28")
      (value "0R")
      (footprint "R0805")
      (description "GENERAL PURPOSE CHIP RESISTOR Metal Glaze/thick Film, 0.125W, 0ohm, Surface Mount, 0805")
      (fields
        (field (name "MANUFACTURER") "Yageo Group")
        (field (name "MANUFACTURER PART NUMBER") "RC0805JR-070RL")
      )
      (libsource (lib "28pins_Antariksh_unoR3_V1I1_PCB") (part "RC0805JR-070RL"))
    )
    (comp (ref "SCKT FOR U1")
      (value "28-DIP Socket")
      (footprint "28-DIP_7.62mm_SOCKET")
      (description "IC Socket, DIP28, 28 Contact(s), 2.54mm Term Pitch, 7.62mm Row Spacing, Solder")
      (fields (field (name "MANUFACTURER") "3M") (field (name "MANUFACTURER PART NUMBER") "4828-3004-CP"))
      (libsource (lib "28pins_Antariksh_unoR3_V1I1_PCB") (part "4828-3004-CP"))
    )
    (comp (ref "SW1")
      (value "1825910-6")
      (footprint "1825910-6")
      (description "Switch Tactile OFF (ON) SPST Round Button PC Pins 0.05A 24VDC 1.57N Thru-Hole Loose")
      (fields (field (name "MANUFACTURER") "TE Connectivity"))
      (libsource (lib "28pins_Antariksh_unoR3_V1I1_PCB") (part "1825910-6"))
    )
    (comp (ref "SW2")
      (value "1825910-6")
      (footprint "1825910-6")
      (description "Switch Tactile OFF (ON) SPST Round Button PC Pins 0.05A 24VDC 1.57N Thru-Hole Loose")
      (fields (field (name "MANUFACTURER") "TE Connectivity"))
      (libsource (lib "28pins_Antariksh_unoR3_V1I1_PCB") (part "1825910-6"))
    )
    (comp (ref "U1")
      (value "ATMEGA328P-PU")
      (footprint "28_DIP_7.62mm")
      (description "Microchip - ATMEGA328P-PU - Microcontroller Mcu, 8 Bit, Atmega, 20MHZ, DIP-28")
      (fields (field (name "MANUFACTURER") "Microchip"))
      (libsource (lib "lec4") (part "ATMEGA328P-PU"))
    )
    (comp (ref "U2")
      (value "ATMEGA16U2-AU")
      (footprint "TQFP32")
      (description "Risc Microcontroller, 8-BIT, Flash, AVR Risc Cpu, 16MHZ, Cmos, PQFP32")
      (fields (field (name "MANUFACTURER") "Microchip"))
      (libsource (lib "28pins_Antariksh_unoR3_V1I1_PCB") (part "ATMEGA16U2-AU"))
    )
    (comp (ref "U3")
      (value "TL1963A-33DCQR")
      (footprint "DCQ (R-PDSO-G6)")
      (description "LDO Regulator Pos 3.3V 1.5A 6-Pin(5+Tab) SOT-223 T/R")
      (fields (field (name "MANUFACTURER") "Texas Instruments"))
      (libsource (lib "28pins_Antariksh_unoR3_V1I1_PCB") (part "TL1963A-33DCQR"))
    )
    (comp (ref "U4")
      (value "SN74AHC1G09DBVR")
      (footprint "DBV_SOP_23_5")
      (description "1-ch, 2-input 2-V to 5.5-V high-speed (9 ns) AND gate with open-drain outputs 5-SOT-23 -55 to 125")
      (fields (field (name "MANUFACTURER") "Texas Instruments"))
      (libsource (lib "28pins_Antariksh_unoR3_V1I1_PCB") (part "SN74AHC1G09DBVR"))
    )
    (comp (ref "U5")
      (value "SN74AHC1G09DBVR")
      (footprint "DBV_SOP_23_5")
      (description "1-ch, 2-input 2-V to 5.5-V high-speed (9 ns) AND gate with open-drain outputs 5-SOT-23 -55 to 125")
      (fields (field (name "MANUFACTURER") "Texas Instruments"))
      (libsource (lib "28pins_Antariksh_unoR3_V1I1_PCB") (part "SN74AHC1G09DBVR"))
    )
    (comp (ref "U6")
      (value "SN74AHC1G09DBVR")
      (footprint "DBV_SOP_23_5")
      (description "1-ch, 2-input 2-V to 5.5-V high-speed (9 ns) AND gate with open-drain outputs 5-SOT-23 -55 to 125")
      (fields (field (name "MANUFACTURER") "Texas Instruments"))
      (libsource (lib "28pins_Antariksh_unoR3_V1I1_PCB") (part "SN74AHC1G09DBVR"))
    )
    (comp (ref "U7")
      (value "SN74AHC1G09DBVR")
      (footprint "DBV_SOP_23_5")
      (description "1-ch, 2-input 2-V to 5.5-V high-speed (9 ns) AND gate with open-drain outputs 5-SOT-23 -55 to 125")
      (fields (field (name "MANUFACTURER") "Texas Instruments"))
      (libsource (lib "28pins_Antariksh_unoR3_V1I1_PCB") (part "SN74AHC1G09DBVR"))
    )
    (comp (ref "Y1")
      (value "ABM7-16.000MHZ-D2Y-T")
      (footprint "ABM7_v1_1_BIG")
      (description "Crystal 16MHz ±20ppm (Tol) ±30ppm (Stability) 18pF FUND 50Ohm 2-Pin Mini-CSMD T/R")
      (fields (field (name "MANUFACTURER") "Abracon") (field (name "TOLERANCE") "0.002%"))
      (libsource (lib "28pins_Antariksh_unoR3_V1I1_PCB") (part "ABM7-16.000MHZ-D2Y-T"))
    )
    (comp (ref "Y2")
      (value "ABM7-16.000MHZ-D2Y-T")
      (footprint "ABM7_v1_1_BIG")
      (description "Crystal 16MHz ±20ppm (Tol) ±30ppm (Stability) 18pF FUND 50Ohm 2-Pin Mini-CSMD T/R")
      (fields (field (name "MANUFACTURER") "Abracon") (field (name "TOLERANCE") "0.002%"))
      (libsource (lib "28pins_Antariksh_unoR3_V1I1_PCB") (part "ABM7-16.000MHZ-D2Y-T"))
    )
    (comp (ref "Z1")
      (value "CG0603MLC-05E")
      (footprint "R0603")
      (description "ESD Suppressor Multilayer Varistor 5V Automotive 2-Pin Case 0603(1608Metric) T/R")
      (fields (field (name "MANUFACTURER") "Bourns") (field (name "VOLTAGE") "5V"))
      (libsource (lib "28pins_Antariksh_unoR3_V1I1_PCB") (part "CG0603MLC-05E"))
    )
    (comp (ref "Z2")
      (value "CG0603MLC-05E")
      (footprint "R0603")
      (description "ESD Suppressor Multilayer Varistor 5V Automotive 2-Pin Case 0603(1608Metric) T/R")
      (fields (field (name "MANUFACTURER") "Bourns") (field (name "VOLTAGE") "5V"))
      (libsource (lib "28pins_Antariksh_unoR3_V1I1_PCB") (part "CG0603MLC-05E"))
    )
  )
  (nets
    (net (code "1") (name "+3V3") (class "Default")
      (node (ref "C13") (pin "2") (pinfunction "2_2") (pintype "passive"))
      (node (ref "C16") (pin "2") (pinfunction "2_2") (pintype "passive"))
      (node (ref "J1") (pin "4") (pinfunction "4_4") (pintype "passive"))
      (node (ref "JP4") (pin "3") (pinfunction "3_3") (pintype "passive"))
      (node (ref "R28") (pin "2") (pinfunction "2_2") (pintype "passive"))
      (node (ref "U3") (pin "4") (pinfunction "OUT_4") (pintype "passive"))
      (node (ref "U3") (pin "5") (pinfunction "SENSE_5") (pintype "passive"))
    )
    (net (code "2") (name "+5V") (class "Default")
      (node (ref "C12") (pin "2") (pinfunction "2_2") (pintype "passive"))
      (node (ref "C14") (pin "2") (pinfunction "2_2") (pintype "passive"))
      (node (ref "C2") (pin "1") (pinfunction "1_1") (pintype "passive"))
      (node (ref "C6") (pin "2") (pinfunction "2_2") (pintype "passive"))
      (node (ref "J1") (pin "5") (pinfunction "5_5") (pintype "passive"))
      (node (ref "J8") (pin "1") (pinfunction "1_1") (pintype "passive"))
      (node (ref "JP4") (pin "1") (pinfunction "1_1") (pintype "passive"))
      (node (ref "L1") (pin "2") (pinfunction "2_2") (pintype "passive"))
      (node (ref "R27") (pin "1") (pinfunction "1_1") (pintype "passive"))
      (node (ref "U2") (pin "31") (pinfunction "UVCC_31") (pintype "passive"))
      (node (ref "U3") (pin "1") (pinfunction "~{SHDN}_1") (pintype "passive"))
      (node (ref "U3") (pin "2") (pinfunction "IN_2") (pintype "passive"))
    )
    (net (code "3") (name "+5V{slash}3V3") (class "Default")
      (node (ref "C15") (pin "2") (pinfunction "2_2") (pintype "passive"))
      (node (ref "C18") (pin "2") (pinfunction "2_2") (pintype "passive"))
      (node (ref "C26") (pin "2") (pinfunction "2_2") (pintype "passive"))
      (node (ref "C28") (pin "2") (pinfunction "2_2") (pintype "passive"))
      (node (ref "C29") (pin "2") (pinfunction "2_2") (pintype "passive"))
      (node (ref "C30") (pin "2") (pinfunction "2_2") (pintype "passive"))
      (node (ref "C34") (pin "2") (pinfunction "2_2") (pintype "passive"))
      (node (ref "C8") (pin "2") (pinfunction "2_2") (pintype "passive"))
      (node (ref "D5") (pin "1") (pinfunction "C_1") (pintype "passive"))
      (node (ref "D6") (pin "1") (pinfunction "C_1") (pintype "passive"))
      (node (ref "FB1") (pin "1") (pinfunction "1_1") (pintype "passive"))
      (node (ref "FB2") (pin "1") (pinfunction "1_1") (pintype "passive"))
      (node (ref "FB3") (pin "1") (pinfunction "1_1") (pintype "passive"))
      (node (ref "J1") (pin "2") (pinfunction "2_2") (pintype "passive"))
      (node (ref "J5") (pin "2") (pinfunction "2_2") (pintype "passive"))
      (node (ref "J6") (pin "2") (pinfunction "2_2") (pintype "passive"))
      (node (ref "JP4") (pin "2") (pinfunction "2_2") (pintype "passive"))
      (node (ref "R1") (pin "2") (pinfunction "2_2") (pintype "passive"))
      (node (ref "R14") (pin "2") (pinfunction "2_2") (pintype "passive"))
      (node (ref "R15") (pin "2") (pinfunction "2_2") (pintype "passive"))
      (node (ref "R17") (pin "2") (pinfunction "2_2") (pintype "passive"))
      (node (ref "R18") (pin "2") (pinfunction "2_2") (pintype "passive"))
      (node (ref "R19") (pin "2") (pinfunction "2_2") (pintype "passive"))
      (node (ref "R2") (pin "2") (pinfunction "2_2") (pintype "passive"))
      (node (ref "R20") (pin "2") (pinfunction "2_2") (pintype "passive"))
      (node (ref "R21") (pin "2") (pinfunction "2_2") (pintype "passive"))
      (node (ref "R27") (pin "2") (pinfunction "2_2") (pintype "passive"))
      (node (ref "R28") (pin "1") (pinfunction "1_1") (pintype "passive"))
      (node (ref "R3") (pin "2") (pinfunction "2_2") (pintype "passive"))
      (node (ref "R4") (pin "2") (pinfunction "2_2") (pintype "passive"))
      (node (ref "U4") (pin "5") (pinfunction "5_5") (pintype "passive"))
      (node (ref "U5") (pin "5") (pinfunction "5_5") (pintype "passive"))
      (node (ref "U6") (pin "5") (pinfunction "5_5") (pintype "passive"))
      (node (ref "U7") (pin "5") (pinfunction "5_5") (pintype "passive"))
    )
    (net (code "4") (name "+AREF") (class "Default")
      (node (ref "C21") (pin "2") (pinfunction "2_2") (pintype "passive"))
      (node (ref "C24") (pin "2") (pinfunction "2_2") (pintype "passive"))
      (node (ref "J4") (pin "8") (pinfunction "8_8") (pintype "passive"))
      (node (ref "U1") (pin "21") (pinfunction "AREF_21") (pintype "passive"))
    )
    (net (code "5") (name "/+3V3 16U2_UCAP") (class "Default")
      (node (ref "C7") (pin "2") (pinfunction "2_2") (pintype "passive"))
      (node (ref "R26") (pin "1") (pinfunction "1_1") (pintype "passive"))
      (node (ref "U2") (pin "27") (pinfunction "UCAP_27") (pintype "passive"))
    )
    (net (code "6") (name "/+5V USB") (class "Default")
      (node (ref "C1") (pin "1") (pinfunction "1_1") (pintype "passive"))
      (node (ref "J7") (pin "1") (pinfunction "1_1") (pintype "passive"))
      (node (ref "L1") (pin "1") (pinfunction "1_1") (pintype "passive"))
    )
    (net (code "7") (name "/+5V{slash}3V3 16U2") (class "Default")
      (node (ref "C3") (pin "2") (pinfunction "2_2") (pintype "passive"))
      (node (ref "C4") (pin "2") (pinfunction "2_2") (pintype "passive"))
      (node (ref "C5") (pin "2") (pinfunction "2_2") (pintype "passive"))
      (node (ref "FB1") (pin "2") (pinfunction "2_2") (pintype "passive"))
      (node (ref "R26") (pin "2") (pinfunction "2_2") (pintype "passive"))
      (node (ref "U2") (pin "32") (pinfunction "AVCC_32") (pintype "passive"))
      (node (ref "U2") (pin "4") (pinfunction "VCC_4") (pintype "passive"))
    )
    (net (code "8") (name "/+5V{slash}3V3 328P_AVCC") (class "Default")
      (node (ref "C22") (pin "2") (pinfunction "2_2") (pintype "passive"))
      (node (ref "C23") (pin "2") (pinfunction "2_2") (pintype "passive"))
      (node (ref "FB3") (pin "2") (pinfunction "2_2") (pintype "passive"))
      (node (ref "U1") (pin "20") (pinfunction "AVCC_20") (pintype "passive"))
    )
    (net (code "9") (name "/+5V{slash}3V3 328P_VCC") (class "Default")
      (node (ref "C19") (pin "2") (pinfunction "2_2") (pintype "passive"))
      (node (ref "C20") (pin "2") (pinfunction "2_2") (pintype "passive"))
      (node (ref "FB2") (pin "2") (pinfunction "2_2") (pintype "passive"))
      (node (ref "U1") (pin "7") (pinfunction "VCC_7") (pintype "passive"))
    )
    (net (code "10") (name "/16U2 16MHz XTAL1") (class "Default")
      (node (ref "C10") (pin "2") (pinfunction "2_2") (pintype "passive"))
      (node (ref "R9") (pin "1") (pinfunction "1_1") (pintype "passive"))
      (node (ref "U2") (pin "1") (pinfunction "XTAL1_1") (pintype "passive"))
      (node (ref "Y2") (pin "1") (pinfunction "1_1") (pintype "passive"))
    )
    (net (code "11") (name "/16U2 16MHz XTAL2") (class "Default")
      (node (ref "C9") (pin "2") (pinfunction "2_2") (pintype "passive"))
      (node (ref "R9") (pin "2") (pinfunction "2_2") (pintype "passive"))
      (node (ref "U2") (pin "2") (pinfunction "(PC0)_XTAL2_2") (pintype "passive"))
      (node (ref "Y2") (pin "2") (pinfunction "2_2") (pintype "passive"))
    )
    (net (code "12") (name "/16U2 PB4") (class "Default")
      (node (ref "JP2") (pin "1") (pinfunction "1_1") (pintype "passive"))
      (node (ref "JP3") (pin "2") (pinfunction "2_2") (pintype "passive"))
      (node (ref "U2") (pin "18") (pinfunction "PB4_(T1_/_PCINT4)_18") (pintype "passive"))
    )
    (net (code "13") (name "/16U2 RESETn") (class "Default")
      (node (ref "JP3") (pin "4") (pinfunction "4_4") (pintype "passive"))
      (node (ref "R4") (pin "1") (pinfunction "1_1") (pintype "passive"))
      (node (ref "U2") (pin "24") (pinfunction "~{RESET}_(PC1_/_dW)_24") (pintype "passive"))
      (node (ref "U5") (pin "4") (pinfunction "4_4") (pintype "passive"))
    )
    (net (code "14") (name "/16U2 RXD") (class "Default")
      (node (ref "R11") (pin "1") (pinfunction "1_1") (pintype "passive"))
      (node (ref "U2") (pin "8") (pinfunction "(RXD1_/_AIN1_/_INT2)_PD2_8") (pintype "passive"))
    )
    (net (code "15") (name "/16U2 RX_LED") (class "Default")
      (node (ref "D4") (pin "1") (pinfunction "C_1") (pintype "passive"))
      (node (ref "U2") (pin "10") (pinfunction "(INT5/_AIN3)_PD4_10") (pintype "passive"))
    )
    (net (code "16") (name "/16U2 SCLK") (class "Default")
      (node (ref "J6") (pin "3") (pinfunction "3_3") (pintype "passive"))
      (node (ref "R5") (pin "2") (pinfunction "2_2") (pintype "passive"))
    )
    (net (code "17") (name "/16U2 TXD") (class "Default")
      (node (ref "R10") (pin "1") (pinfunction "1_1") (pintype "passive"))
      (node (ref "U2") (pin "9") (pinfunction "(TXD1_/_INT3)_PD3_9") (pintype "passive"))
    )
    (net (code "18") (name "/16U2 TX_LED") (class "Default")
      (node (ref "D3") (pin "1") (pinfunction "C_1") (pintype "passive"))
      (node (ref "U2") (pin "11") (pinfunction "(XCK_/_AIN4_/_PCINT12)_PD5_11") (pintype "passive"))
    )
    (net (code "19") (name "/16U2PROG 328P RESETn") (class "Default")
      (node (ref "JP1") (pin "2") (pinfunction "2_2") (pintype "passive"))
      (node (ref "R1") (pin "1") (pinfunction "1_1") (pintype "passive"))
      (node (ref "U2") (pin "13") (pinfunction "(~{CTS}_/_~{HWB}_/_AIN6_/_T0_/_INT7)_PD7_13") (pintype "passive"))
    )
    (net (code "20") (name "/16U2_BUF_RESET") (class "Default")
      (node (ref "C31") (pin "2") (pinfunction "2_2") (pintype "passive"))
      (node (ref "R23") (pin "2") (pinfunction "2_2") (pintype "passive"))
      (node (ref "U5") (pin "1") (pinfunction "1_1") (pintype "passive"))
      (node (ref "U5") (pin "2") (pinfunction "2_2") (pintype "passive"))
    )
    (net (code "21") (name "/16U2_HDR_RESETn") (class "Default")
      (node (ref "J6") (pin "5") (pinfunction "5_5") (pintype "passive"))
      (node (ref "JP3") (pin "3") (pinfunction "3_3") (pintype "passive"))
    )
    (net (code "22") (name "/16U2_MISO") (class "Default")
      (node (ref "J6") (pin "1") (pinfunction "1_1") (pintype "passive"))
      (node (ref "U2") (pin "17") (pinfunction "PB3_(PDO_/_MISO_/_PCINT3)_17") (pintype "passive"))
    )
    (net (code "23") (name "/16U2_MOSI") (class "Default")
      (node (ref "J6") (pin "4") (pinfunction "4_4") (pintype "passive"))
      (node (ref "U2") (pin "16") (pinfunction "(PDI_/_MOSI_/_PCINT2)_PB2_16") (pintype "passive"))
    )
    (net (code "24") (name "/16U2_PB5") (class "Default")
      (node (ref "JP2") (pin "3") (pinfunction "3_3") (pintype "passive"))
      (node (ref "U2") (pin "19") (pinfunction "PB5_(PCINT5)_19") (pintype "passive"))
    )
    (net (code "25") (name "/16U2_PB6") (class "Default")
      (node (ref "JP2") (pin "2") (pinfunction "2_2") (pintype "passive"))
      (node (ref "U2") (pin "20") (pinfunction "PB6_(PCINT6)_20") (pintype "passive"))
    )
    (net (code "26") (name "/16U2_PB7") (class "Default")
      (node (ref "JP2") (pin "4") (pinfunction "4_4") (pintype "passive"))
      (node (ref "U2") (pin "21") (pinfunction "PB7_(PCINT7_/_OC.0A_/_OC.1C)_21") (pintype "passive"))
    )
    (net (code "27") (name "/16U2_SCLK_R") (class "Default")
      (node (ref "R5") (pin "1") (pinfunction "1_1") (pintype "passive"))
      (node (ref "U2") (pin "15") (pinfunction "(SCLK_/_PCINT1)_PB1_15") (pintype "passive"))
    )
    (net (code "28") (name "/328P 16MHz XTAL1") (class "Default")
      (node (ref "C27") (pin "2") (pinfunction "2_2") (pintype "passive"))
      (node (ref "R16") (pin "1") (pinfunction "1_1") (pintype "passive"))
      (node (ref "U1") (pin "9") (pinfunction "PB6/PCINT6/XTAL1/TOSC1_9") (pintype "passive"))
      (node (ref "Y1") (pin "1") (pinfunction "1_1") (pintype "passive"))
    )
    (net (code "29") (name "/328P 16MHz XTAL2") (class "Default")
      (node (ref "C25") (pin "2") (pinfunction "2_2") (pintype "passive"))
      (node (ref "R16") (pin "2") (pinfunction "2_2") (pintype "passive"))
      (node (ref "U1") (pin "10") (pinfunction "PB7/PCINT7/XTAL2/TOSC2_10") (pintype "passive"))
      (node (ref "Y1") (pin "2") (pinfunction "2_2") (pintype "passive"))
    )
    (net (code "30") (name "/328P AUTORESETn") (class "Default")
      (node (ref "C11") (pin "2") (pinfunction "2_2") (pintype "passive"))
      (node (ref "R18") (pin "1") (pinfunction "1_1") (pintype "passive"))
      (node (ref "U6") (pin "1") (pinfunction "1_1") (pintype "passive"))
    )
    (net (code "31") (name "/328P RESETn") (class "Default")
      (node (ref "J1") (pin "3") (pinfunction "3_3") (pintype "passive"))
      (node (ref "J5") (pin "5") (pinfunction "5_5") (pintype "passive"))
      (node (ref "JP3") (pin "1") (pinfunction "1_1") (pintype "passive"))
      (node (ref "R14") (pin "1") (pinfunction "1_1") (pintype "passive"))
      (node (ref "U1") (pin "1") (pinfunction "PC6/PCINT14/~{RESET}_1") (pintype "passive"))
      (node (ref "U6") (pin "4") (pinfunction "4_4") (pintype "passive"))
    )
    (net (code "32") (name "/328P_BUF_RESET") (class "Default")
      (node (ref "C32") (pin "2") (pinfunction "2_2") (pintype "passive"))
      (node (ref "R24") (pin "2") (pinfunction "2_2") (pintype "passive"))
      (node (ref "U6") (pin "2") (pinfunction "2_2") (pintype "passive"))
    )
    (net (code "33") (name "/AD0") (class "Default")
      (node (ref "J2") (pin "1") (pinfunction "1_1") (pintype "passive"))
      (node (ref "U1") (pin "23") (pinfunction "ADC0/PCINT8/PC0_23") (pintype "passive"))
    )
    (net (code "34") (name "/AD1") (class "Default")
      (node (ref "J2") (pin "2") (pinfunction "2_2") (pintype "passive"))
      (node (ref "U1") (pin "24") (pinfunction "ADC1/PCINT9/PC1_24") (pintype "passive"))
    )
    (net (code "35") (name "/AD2") (class "Default")
      (node (ref "J2") (pin "3") (pinfunction "3_3") (pintype "passive"))
      (node (ref "U1") (pin "25") (pinfunction "ADC2/PCINT10/PC2_25") (pintype "passive"))
    )
    (net (code "36") (name "/AD3") (class "Default")
      (node (ref "J2") (pin "4") (pinfunction "4_4") (pintype "passive"))
      (node (ref "U1") (pin "26") (pinfunction "ADC3/PCINT11/PC3_26") (pintype "passive"))
    )
    (net (code "37") (name "/AD4{slash}SDA") (class "Default")
      (node (ref "J2") (pin "5") (pinfunction "5_5") (pintype "passive"))
      (node (ref "J4") (pin "9") (pinfunction "9_9") (pintype "passive"))
      (node (ref "U1") (pin "27") (pinfunction "SDA/ADC4/PCINT12/PC4_27") (pintype "passive"))
    )
    (net (code "38") (name "/AD5{slash}SCL") (class "Default")
      (node (ref "J2") (pin "6") (pinfunction "6_6") (pintype "passive"))
      (node (ref "J4") (pin "10") (pinfunction "10_10") (pintype "passive"))
      (node (ref "U1") (pin "28") (pinfunction "SCL/ADC5/PCINT13/PC5_28") (pintype "passive"))
    )
    (net (code "39") (name "/BUTTON RESETn") (class "Default")
      (node (ref "D6") (pin "2") (pinfunction "A_2") (pintype "passive"))
      (node (ref "R20") (pin "1") (pinfunction "1_1") (pintype "passive"))
      (node (ref "R24") (pin "1") (pinfunction "1_1") (pintype "passive"))
      (node (ref "SW1") (pin "1") (pinfunction "1_1") (pintype "passive"))
      (node (ref "SW1") (pin "2") (pinfunction "2_2") (pintype "passive"))
    )
    (net (code "40") (name "/CON_USB_N") (class "Default")
      (node (ref "J7") (pin "2") (pinfunction "2_2") (pintype "passive"))
      (node (ref "R6") (pin "1") (pinfunction "1_1") (pintype "passive"))
      (node (ref "Z1") (pin "2") (pinfunction "2_2") (pintype "passive"))
    )
    (net (code "41") (name "/CON_USB_P") (class "Default")
      (node (ref "J7") (pin "3") (pinfunction "3_3") (pintype "passive"))
      (node (ref "R7") (pin "1") (pinfunction "1_1") (pintype "passive"))
      (node (ref "Z2") (pin "2") (pinfunction "2_2") (pintype "passive"))
    )
    (net (code "42") (name "/IO0") (class "Default")
      (node (ref "J3") (pin "1") (pinfunction "1_1") (pintype "passive"))
      (node (ref "R10") (pin "2") (pinfunction "2_2") (pintype "passive"))
      (node (ref "U1") (pin "2") (pinfunction "PCINT16/RXD/PD0_2") (pintype "passive"))
    )
    (net (code "43") (name "/IO1") (class "Default")
      (node (ref "J3") (pin "2") (pinfunction "2_2") (pintype "passive"))
      (node (ref "R11") (pin "2") (pinfunction "2_2") (pintype "passive"))
      (node (ref "U1") (pin "3") (pinfunction "TXD/PCINT17/PD1_3") (pintype "passive"))
    )
    (net (code "44") (name "/IO2") (class "Default")
      (node (ref "J3") (pin "3") (pinfunction "3_3") (pintype "passive"))
      (node (ref "U1") (pin "4") (pinfunction "INT0/PCINT18/PD2_4") (pintype "passive"))
    )
    (net (code "45") (name "/IO3") (class "Default")
      (node (ref "J3") (pin "4") (pinfunction "4_4") (pintype "passive"))
      (node (ref "U1") (pin "5") (pinfunction "OC2B/INT1/PCINT19/PD3_5") (pintype "passive"))
    )
    (net (code "46") (name "/IO4") (class "Default")
      (node (ref "J3") (pin "5") (pinfunction "5_5") (pintype "passive"))
      (node (ref "U1") (pin "6") (pinfunction "XCK/T0/PCINT20/PD4_6") (pintype "passive"))
    )
    (net (code "47") (name "/IO5") (class "Default")
      (node (ref "J3") (pin "6") (pinfunction "6_6") (pintype "passive"))
      (node (ref "U1") (pin "11") (pinfunction "OC0B/T1/PCINT21/PD5_11") (pintype "passive"))
    )
    (net (code "48") (name "/IO6") (class "Default")
      (node (ref "J3") (pin "7") (pinfunction "7_7") (pintype "passive"))
      (node (ref "U1") (pin "12") (pinfunction "OC0A/A1N0/PCINT22/PD6_12") (pintype "passive"))
    )
    (net (code "49") (name "/IO7") (class "Default")
      (node (ref "J3") (pin "8") (pinfunction "8_8") (pintype "passive"))
      (node (ref "U1") (pin "13") (pinfunction "A1N1/PCINT23/PD7_13") (pintype "passive"))
    )
    (net (code "50") (name "/IO8") (class "Default")
      (node (ref "J4") (pin "1") (pinfunction "1_1") (pintype "passive"))
      (node (ref "R22") (pin "2") (pinfunction "2_2") (pintype "passive"))
      (node (ref "U1") (pin "14") (pinfunction "CLKO/PCINT0/ICP1/PB0_14") (pintype "passive"))
    )
    (net (code "51") (name "/IO9") (class "Default")
      (node (ref "J4") (pin "2") (pinfunction "2_2") (pintype "passive"))
      (node (ref "U1") (pin "15") (pinfunction "OC1A/PCINT1/PB1_15") (pintype "passive"))
    )
    (net (code "52") (name "/MISO") (class "Default")
      (node (ref "J4") (pin "5") (pinfunction "5_5") (pintype "passive"))
      (node (ref "J5") (pin "1") (pinfunction "1_1") (pintype "passive"))
      (node (ref "U1") (pin "18") (pinfunction "MISO/PCINT4/PB4_18") (pintype "passive"))
    )
    (net (code "53") (name "/MOSI") (class "Default")
      (node (ref "J4") (pin "4") (pinfunction "4_4") (pintype "passive"))
      (node (ref "J5") (pin "4") (pinfunction "4_4") (pintype "passive"))
      (node (ref "U1") (pin "17") (pinfunction "MOSI/OC2A/PCINT3/PB3_17") (pintype "passive"))
    )
    (net (code "54") (name "/SCK") (class "Default")
      (node (ref "J4") (pin "6") (pinfunction "6_6") (pintype "passive"))
      (node (ref "J5") (pin "3") (pinfunction "3_3") (pintype "passive"))
      (node (ref "R13") (pin "2") (pinfunction "2_2") (pintype "passive"))
      (node (ref "U4") (pin "1") (pinfunction "1_1") (pintype "passive"))
      (node (ref "U4") (pin "2") (pinfunction "2_2") (pintype "passive"))
    )
    (net (code "55") (name "/SCK_R") (class "Default")
      (node (ref "R13") (pin "1") (pinfunction "1_1") (pintype "passive"))
      (node (ref "U1") (pin "19") (pinfunction "SCK/PCINT5/PB5_19") (pintype "passive"))
    )
    (net (code "56") (name "/SS") (class "Default")
      (node (ref "J4") (pin "3") (pinfunction "3_3") (pintype "passive"))
      (node (ref "U1") (pin "16") (pinfunction "~{SS}/OC1B/PCINT2/PB2_16") (pintype "passive"))
    )
    (net (code "57") (name "/USB_N") (class "Default")
      (node (ref "R6") (pin "2") (pinfunction "2_2") (pintype "passive"))
      (node (ref "U2") (pin "30") (pinfunction "D-_30") (pintype "passive"))
    )
    (net (code "58") (name "/USB_P") (class "Default")
      (node (ref "R7") (pin "2") (pinfunction "2_2") (pintype "passive"))
      (node (ref "U2") (pin "29") (pinfunction "D+_29") (pintype "passive"))
    )
    (net (code "59") (name "/USER BUTTON") (class "Default")
      (node (ref "R21") (pin "1") (pinfunction "1_1") (pintype "passive"))
      (node (ref "R25") (pin "1") (pinfunction "1_1") (pintype "passive"))
      (node (ref "SW2") (pin "1") (pinfunction "1_1") (pintype "passive"))
      (node (ref "SW2") (pin "2") (pinfunction "2_2") (pintype "passive"))
    )
    (net (code "60") (name "/USER BUTTON_BUF") (class "Default")
      (node (ref "C33") (pin "2") (pinfunction "2_2") (pintype "passive"))
      (node (ref "R25") (pin "2") (pinfunction "2_2") (pintype "passive"))
      (node (ref "U7") (pin "1") (pinfunction "1_1") (pintype "passive"))
      (node (ref "U7") (pin "2") (pinfunction "2_2") (pintype "passive"))
    )
    (net (code "61") (name "GND") (class "Default")
      (node (ref "C1") (pin "2") (pinfunction "2_2") (pintype "passive"))
      (node (ref "C10") (pin "1") (pinfunction "1_1") (pintype "passive"))
      (node (ref "C12") (pin "1") (pinfunction "1_1") (pintype "passive"))
      (node (ref "C13") (pin "1") (pinfunction "1_1") (pintype "passive"))
      (node (ref "C14") (pin "1") (pinfunction "1_1") (pintype "passive"))
      (node (ref "C15") (pin "1") (pinfunction "1_1") (pintype "passive"))
      (node (ref "C16") (pin "1") (pinfunction "1_1") (pintype "passive"))
      (node (ref "C18") (pin "1") (pinfunction "1_1") (pintype "passive"))
      (node (ref "C19") (pin "1") (pinfunction "1_1") (pintype "passive"))
      (node (ref "C2") (pin "2") (pinfunction "2_2") (pintype "passive"))
      (node (ref "C20") (pin "1") (pinfunction "1_1") (pintype "passive"))
      (node (ref "C21") (pin "1") (pinfunction "1_1") (pintype "passive"))
      (node (ref "C22") (pin "1") (pinfunction "1_1") (pintype "passive"))
      (node (ref "C23") (pin "1") (pinfunction "1_1") (pintype "passive"))
      (node (ref "C24") (pin "1") (pinfunction "1_1") (pintype "passive"))
      (node (ref "C25") (pin "1") (pinfunction "1_1") (pintype "passive"))
      (node (ref "C26") (pin "1") (pinfunction "1_1") (pintype "passive"))
      (node (ref "C27") (pin "1") (pinfunction "1_1") (pintype "passive"))
      (node (ref "C28") (pin "1") (pinfunction "1_1") (pintype "passive"))
      (node (ref "C29") (pin "1") (pinfunction "1_1") (pintype "passive"))
      (node (ref "C3") (pin "1") (pinfunction "1_1") (pintype "passive"))
      (node (ref "C30") (pin "1") (pinfunction "1_1") (pintype "passive"))
      (node (ref "C31") (pin "1") (pinfunction "1_1") (pintype "passive"))
      (node (ref "C32") (pin "1") (pinfunction "1_1") (pintype "passive"))
      (node (ref "C33") (pin "1") (pinfunction "1_1") (pintype "passive"))
      (node (ref "C34") (pin "1") (pinfunction "1_1") (pintype "passive"))
      (node (ref "C4") (pin "1") (pinfunction "1_1") (pintype "passive"))
      (node (ref "C5") (pin "1") (pinfunction "1_1") (pintype "passive"))
      (node (ref "C6") (pin "1") (pinfunction "1_1") (pintype "passive"))
      (node (ref "C7") (pin "1") (pinfunction "1_1") (pintype "passive"))
      (node (ref "C8") (pin "1") (pinfunction "1_1") (pintype "passive"))
      (node (ref "C9") (pin "1") (pinfunction "1_1") (pintype "passive"))
      (node (ref "D1") (pin "1") (pinfunction "C_1") (pintype "passive"))
      (node (ref "J1") (pin "6") (pinfunction "6_6") (pintype "passive"))
      (node (ref "J1") (pin "7") (pinfunction "7_7") (pintype "passive"))
      (node (ref "J4") (pin "7") (pinfunction "7_7") (pintype "passive"))
      (node (ref "J5") (pin "6") (pinfunction "6_6") (pintype "passive"))
      (node (ref "J6") (pin "6") (pinfunction "6_6") (pintype "passive"))
      (node (ref "J7") (pin "10") (pinfunction "10_10") (pintype "passive"))
      (node (ref "J7") (pin "11") (pinfunction "11_11") (pintype "passive"))
      (node (ref "J7") (pin "5") (pinfunction "5_5") (pintype "passive"))
      (node (ref "J7") (pin "6") (pinfunction "6_6") (pintype "passive"))
      (node (ref "J7") (pin "7") (pinfunction "7_7") (pintype "passive"))
      (node (ref "J7") (pin "8") (pinfunction "8_8") (pintype "passive"))
      (node (ref "J7") (pin "9") (pinfunction "9_9") (pintype "passive"))
      (node (ref "J9") (pin "1") (pinfunction "1_1") (pintype "passive"))
      (node (ref "MH1") (pin "1") (pinfunction "1_1") (pintype "passive"))
      (node (ref "MH2") (pin "1") (pinfunction "1_1") (pintype "passive"))
      (node (ref "MH3") (pin "1") (pinfunction "1_1") (pintype "passive"))
      (node (ref "R12") (pin "1") (pinfunction "1_1") (pintype "passive"))
      (node (ref "R8") (pin "2") (pinfunction "2_2") (pintype "passive"))
      (node (ref "SW1") (pin "3") (pinfunction "3_3") (pintype "passive"))
      (node (ref "SW1") (pin "4") (pinfunction "4_4") (pintype "passive"))
      (node (ref "SW2") (pin "3") (pinfunction "3_3") (pintype "passive"))
      (node (ref "SW2") (pin "4") (pinfunction "4_4") (pintype "passive"))
      (node (ref "U1") (pin "22") (pinfunction "GND_2_22") (pintype "passive"))
      (node (ref "U1") (pin "8") (pinfunction "GND_1_8") (pintype "passive"))
      (node (ref "U2") (pin "28") (pinfunction "UGND_28") (pintype "passive"))
      (node (ref "U2") (pin "3") (pinfunction "GND_3") (pintype "passive"))
      (node (ref "U3") (pin "3") (pinfunction "GND_3") (pintype "passive"))
      (node (ref "U3") (pin "6") (pinfunction "EPAD_6") (pintype "passive"))
      (node (ref "U4") (pin "3") (pinfunction "3_3") (pintype "passive"))
      (node (ref "U5") (pin "3") (pinfunction "3_3") (pintype "passive"))
      (node (ref "U6") (pin "3") (pinfunction "3_3") (pintype "passive"))
      (node (ref "U7") (pin "3") (pinfunction "3_3") (pintype "passive"))
      (node (ref "Z1") (pin "1") (pinfunction "1_1") (pintype "passive"))
      (node (ref "Z2") (pin "1") (pinfunction "1_1") (pintype "passive"))
    )
    (net (code "62") (name "Net-(C11-Pad1)") (class "Default")
      (node (ref "C11") (pin "1") (pinfunction "1_1") (pintype "passive"))
      (node (ref "JP1") (pin "1") (pinfunction "1_1") (pintype "passive"))
    )
    (net (code "63") (name "Net-(D1-A)") (class "Default")
      (node (ref "D1") (pin "2") (pinfunction "A_2") (pintype "passive"))
      (node (ref "R17") (pin "1") (pinfunction "1_1") (pintype "passive"))
    )
    (net (code "64") (name "Net-(D2-A)") (class "Default")
      (node (ref "D2") (pin "2") (pinfunction "A_2") (pintype "passive"))
      (node (ref "R15") (pin "1") (pinfunction "1_1") (pintype "passive"))
    )
    (net (code "65") (name "Net-(D2-C)") (class "Default")
      (node (ref "D2") (pin "1") (pinfunction "C_1") (pintype "passive"))
      (node (ref "U4") (pin "4") (pinfunction "4_4") (pintype "passive"))
    )
    (net (code "66") (name "Net-(D3-A)") (class "Default")
      (node (ref "D3") (pin "2") (pinfunction "A_2") (pintype "passive"))
      (node (ref "R2") (pin "1") (pinfunction "1_1") (pintype "passive"))
    )
    (net (code "67") (name "Net-(D4-A)") (class "Default")
      (node (ref "D4") (pin "2") (pinfunction "A_2") (pintype "passive"))
      (node (ref "R3") (pin "1") (pinfunction "1_1") (pintype "passive"))
    )
    (net (code "68") (name "Net-(D5-A)") (class "Default")
      (node (ref "D5") (pin "2") (pinfunction "A_2") (pintype "passive"))
      (node (ref "R19") (pin "1") (pinfunction "1_1") (pintype "passive"))
      (node (ref "R23") (pin "1") (pinfunction "1_1") (pintype "passive"))
    )
    (net (code "69") (name "Net-(J7-Pad4)") (class "Default")
      (node (ref "J7") (pin "4") (pinfunction "4_4") (pintype "passive"))
      (node (ref "R8") (pin "1") (pinfunction "1_1") (pintype "passive"))
    )
    (net (code "70") (name "Net-(JP1-Pad3)") (class "Default")
      (node (ref "JP1") (pin "3") (pinfunction "3_3") (pintype "passive"))
      (node (ref "R12") (pin "2") (pinfunction "2_2") (pintype "passive"))
    )
    (net (code "71") (name "Net-(R22-Pad1)") (class "Default")
      (node (ref "R22") (pin "1") (pinfunction "1_1") (pintype "passive"))
      (node (ref "U7") (pin "4") (pinfunction "4_4") (pintype "passive"))
    )
    (net (code "72") (name "unconnected-(J1-Pad1)") (class "Default")
      (node (ref "J1") (pin "1") (pinfunction "1_1") (pintype "passive+no_connect"))
    )
    (net (code "73") (name "unconnected-(J1-Pad8)") (class "Default")
      (node (ref "J1") (pin "8") (pinfunction "8_8") (pintype "passive+no_connect"))
    )
    (net (code "74") (name "unconnected-(MH4-Pad1)") (class "Default")
      (node (ref "MH4") (pin "1") (pinfunction "1_1") (pintype "passive+no_connect"))
    )
    (net (code "75") (name "unconnected-(U2-(AIN0_{slash}_INT1)_PD1-Pad7)") (class "Default")
      (node (ref "U2") (pin "7") (pinfunction "(AIN0_/_INT1)_PD1_7") (pintype "passive+no_connect"))
    )
    (net (code "76") (name "unconnected-(U2-(OC.0B_{slash}_INT0)_PD0-Pad6)") (class "Default")
      (node (ref "U2") (pin "6") (pinfunction "(OC.0B_/_INT0)_PD0_6") (pintype "passive+no_connect"))
    )
    (net (code "77") (name "unconnected-(U2-(PCINT11_{slash}_AIN2_)_PC2-Pad5)") (class "Default")
      (node (ref "U2") (pin "5") (pinfunction "(PCINT11_/_AIN2_)_PC2_5") (pintype "passive+no_connect"))
    )
    (net (code "78") (name "unconnected-(U2-(~{RTS}_{slash}_AIN5_{slash}_INT6)_PD6-Pad12)") (class "Default")
      (node (ref "U2") (pin "12") (pinfunction "(~{RTS}_/_AIN5_/_INT6)_PD6_12") (pintype "passive+no_connect"))
    )
    (net (code "79") (name "unconnected-(U2-(~{SS}_{slash}_PCINT0)_PB0-Pad14)") (class "Default")
      (node (ref "U2") (pin "14") (pinfunction "(~{SS}_/_PCINT0)_PB0_14") (pintype "passive+no_connect"))
    )
    (net (code "80") (name "unconnected-(U2-PC4_(PCINT10)-Pad26)") (class "Default")
      (node (ref "U2") (pin "26") (pinfunction "PC4_(PCINT10)_26") (pintype "passive+no_connect"))
    )
    (net (code "81") (name "unconnected-(U2-PC5_(_PCINT9{slash}_OC.1B)-Pad25)") (class "Default")
      (node (ref "U2") (pin "25") (pinfunction "PC5_(_PCINT9/_OC.1B)_25") (pintype "passive+no_connect"))
    )
    (net (code "82") (name "unconnected-(U2-PC6_(OC.1A_{slash}_PCINT8)-Pad23)") (class "Default")
      (node (ref "U2") (pin "23") (pinfunction "PC6_(OC.1A_/_PCINT8)_23") (pintype "passive+no_connect"))
    )
    (net (code "83") (name "unconnected-(U2-PC7_(INT4_{slash}_ICP1_{slash}_CLKO)-Pad22)") (class "Default")
      (node (ref "U2") (pin "22") (pinfunction "PC7_(INT4_/_ICP1_/_CLKO)_22") (pintype "passive+no_connect"))
    )
  )
)
